# TMCM-1110_V21_eagle.net
KiCad netlist of a schematic drawn in EAGLE
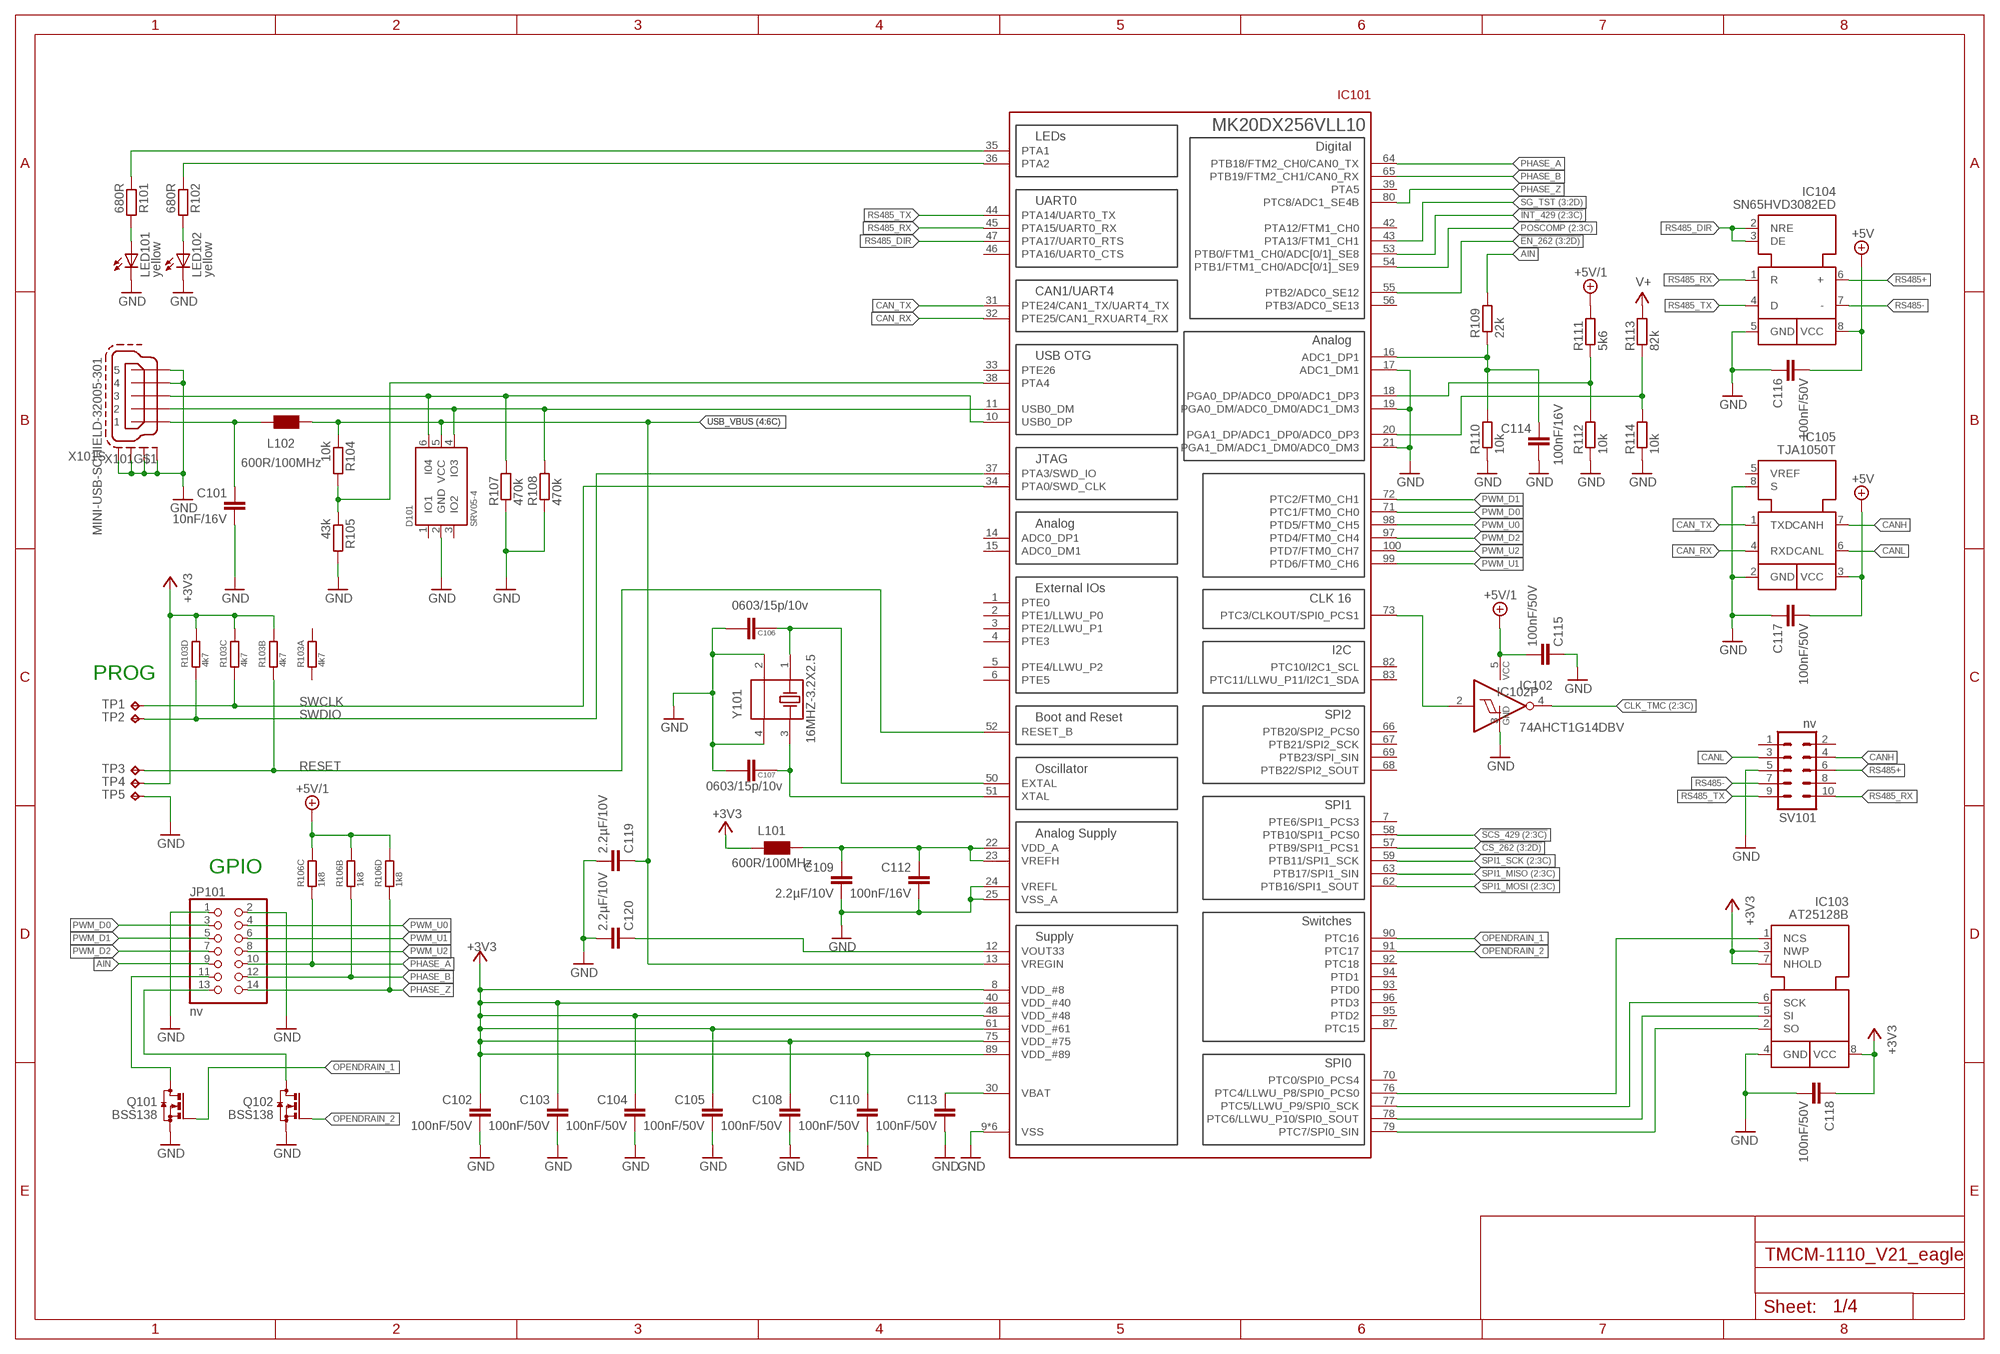
[diagram p0: schematic, sheet 1]
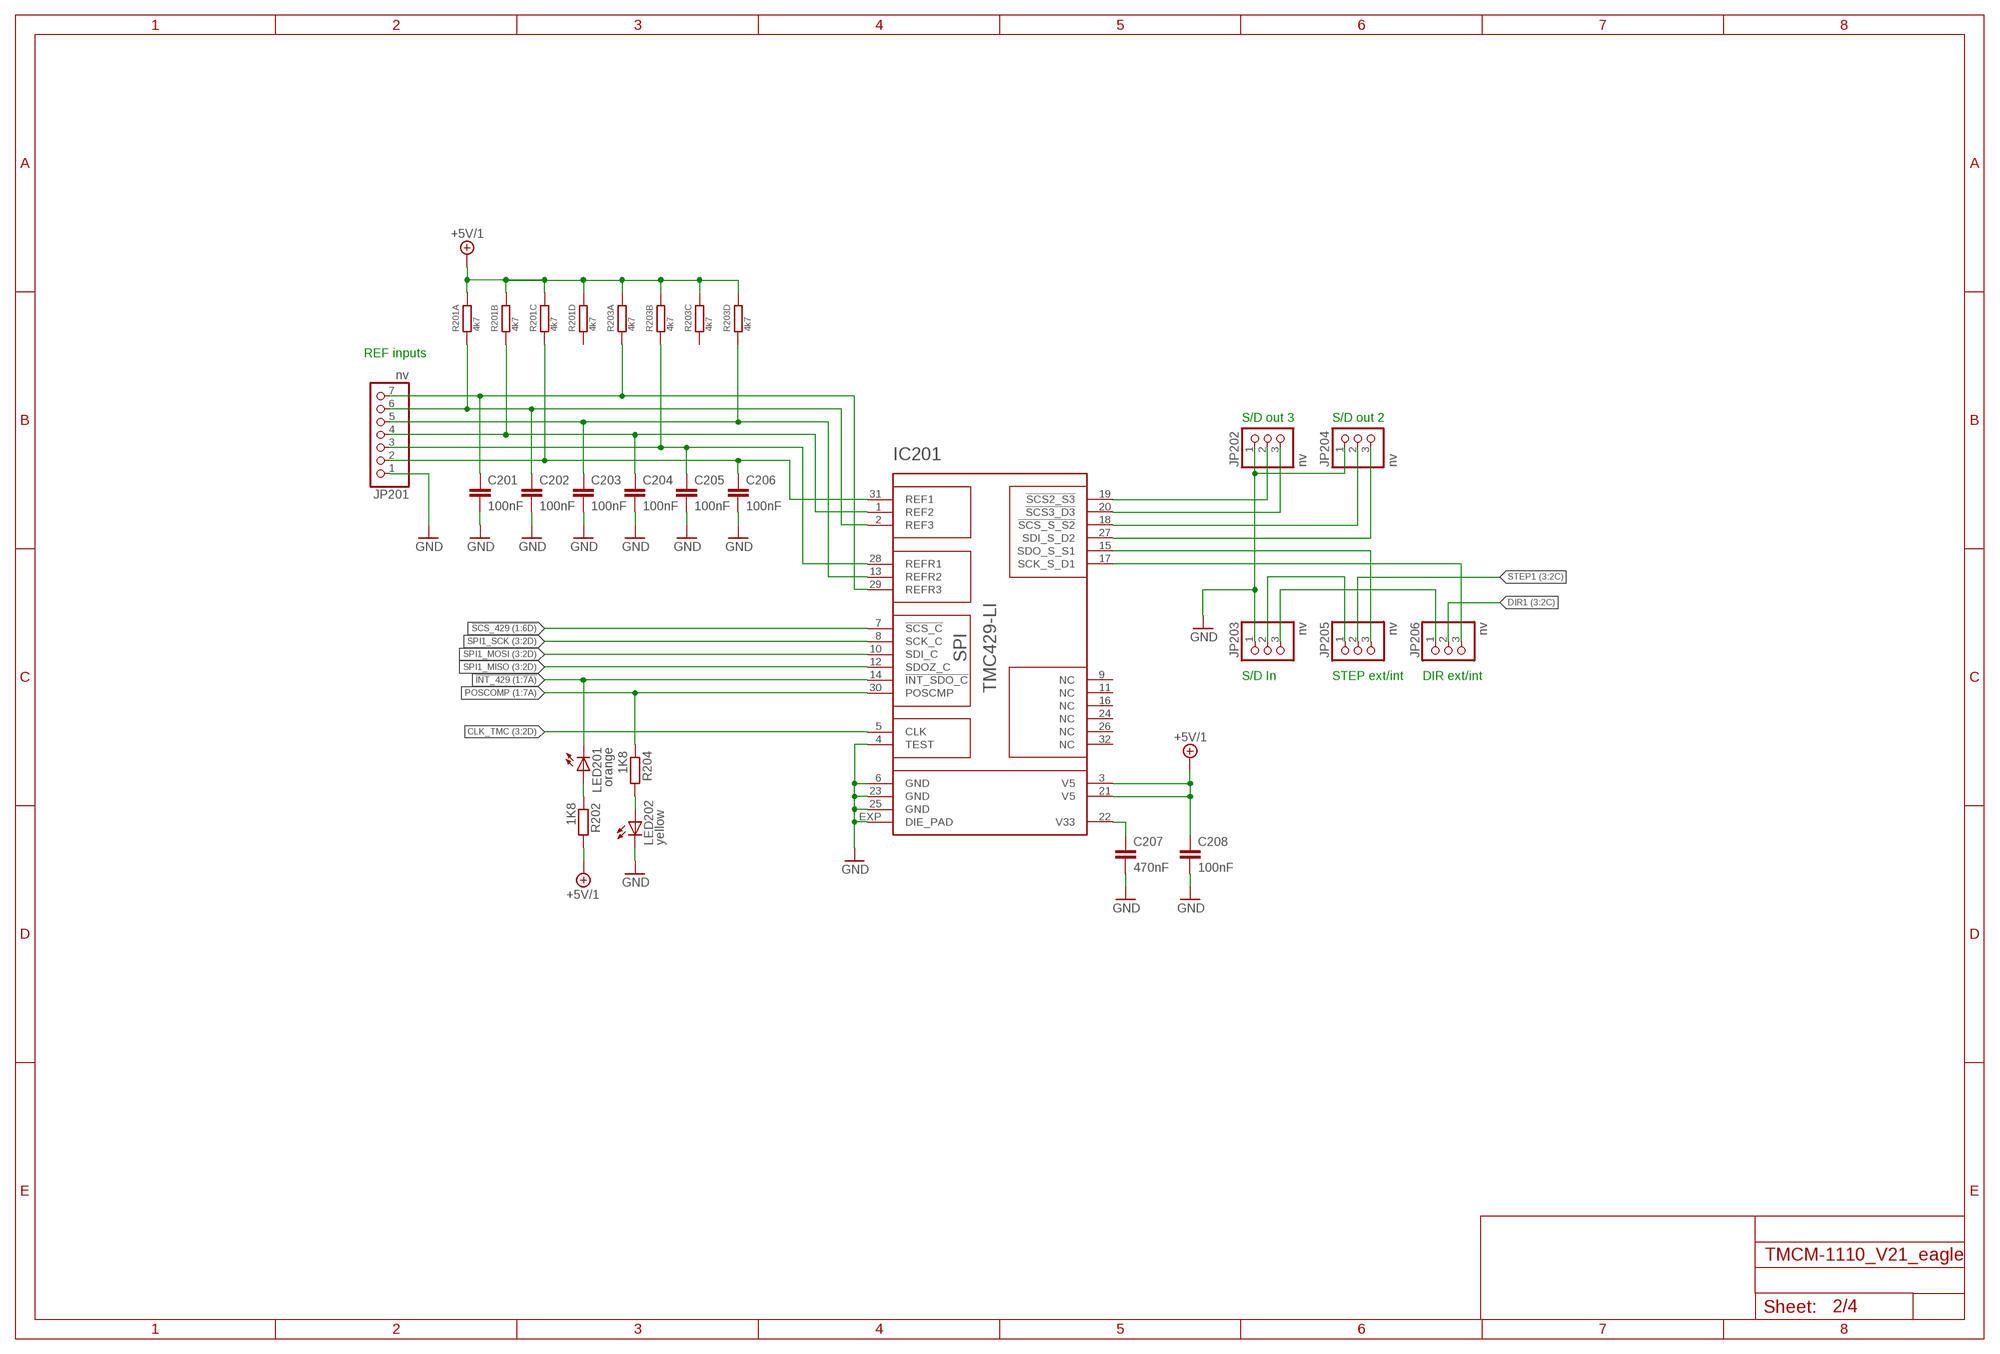
[diagram p1: schematic, sheet 2]
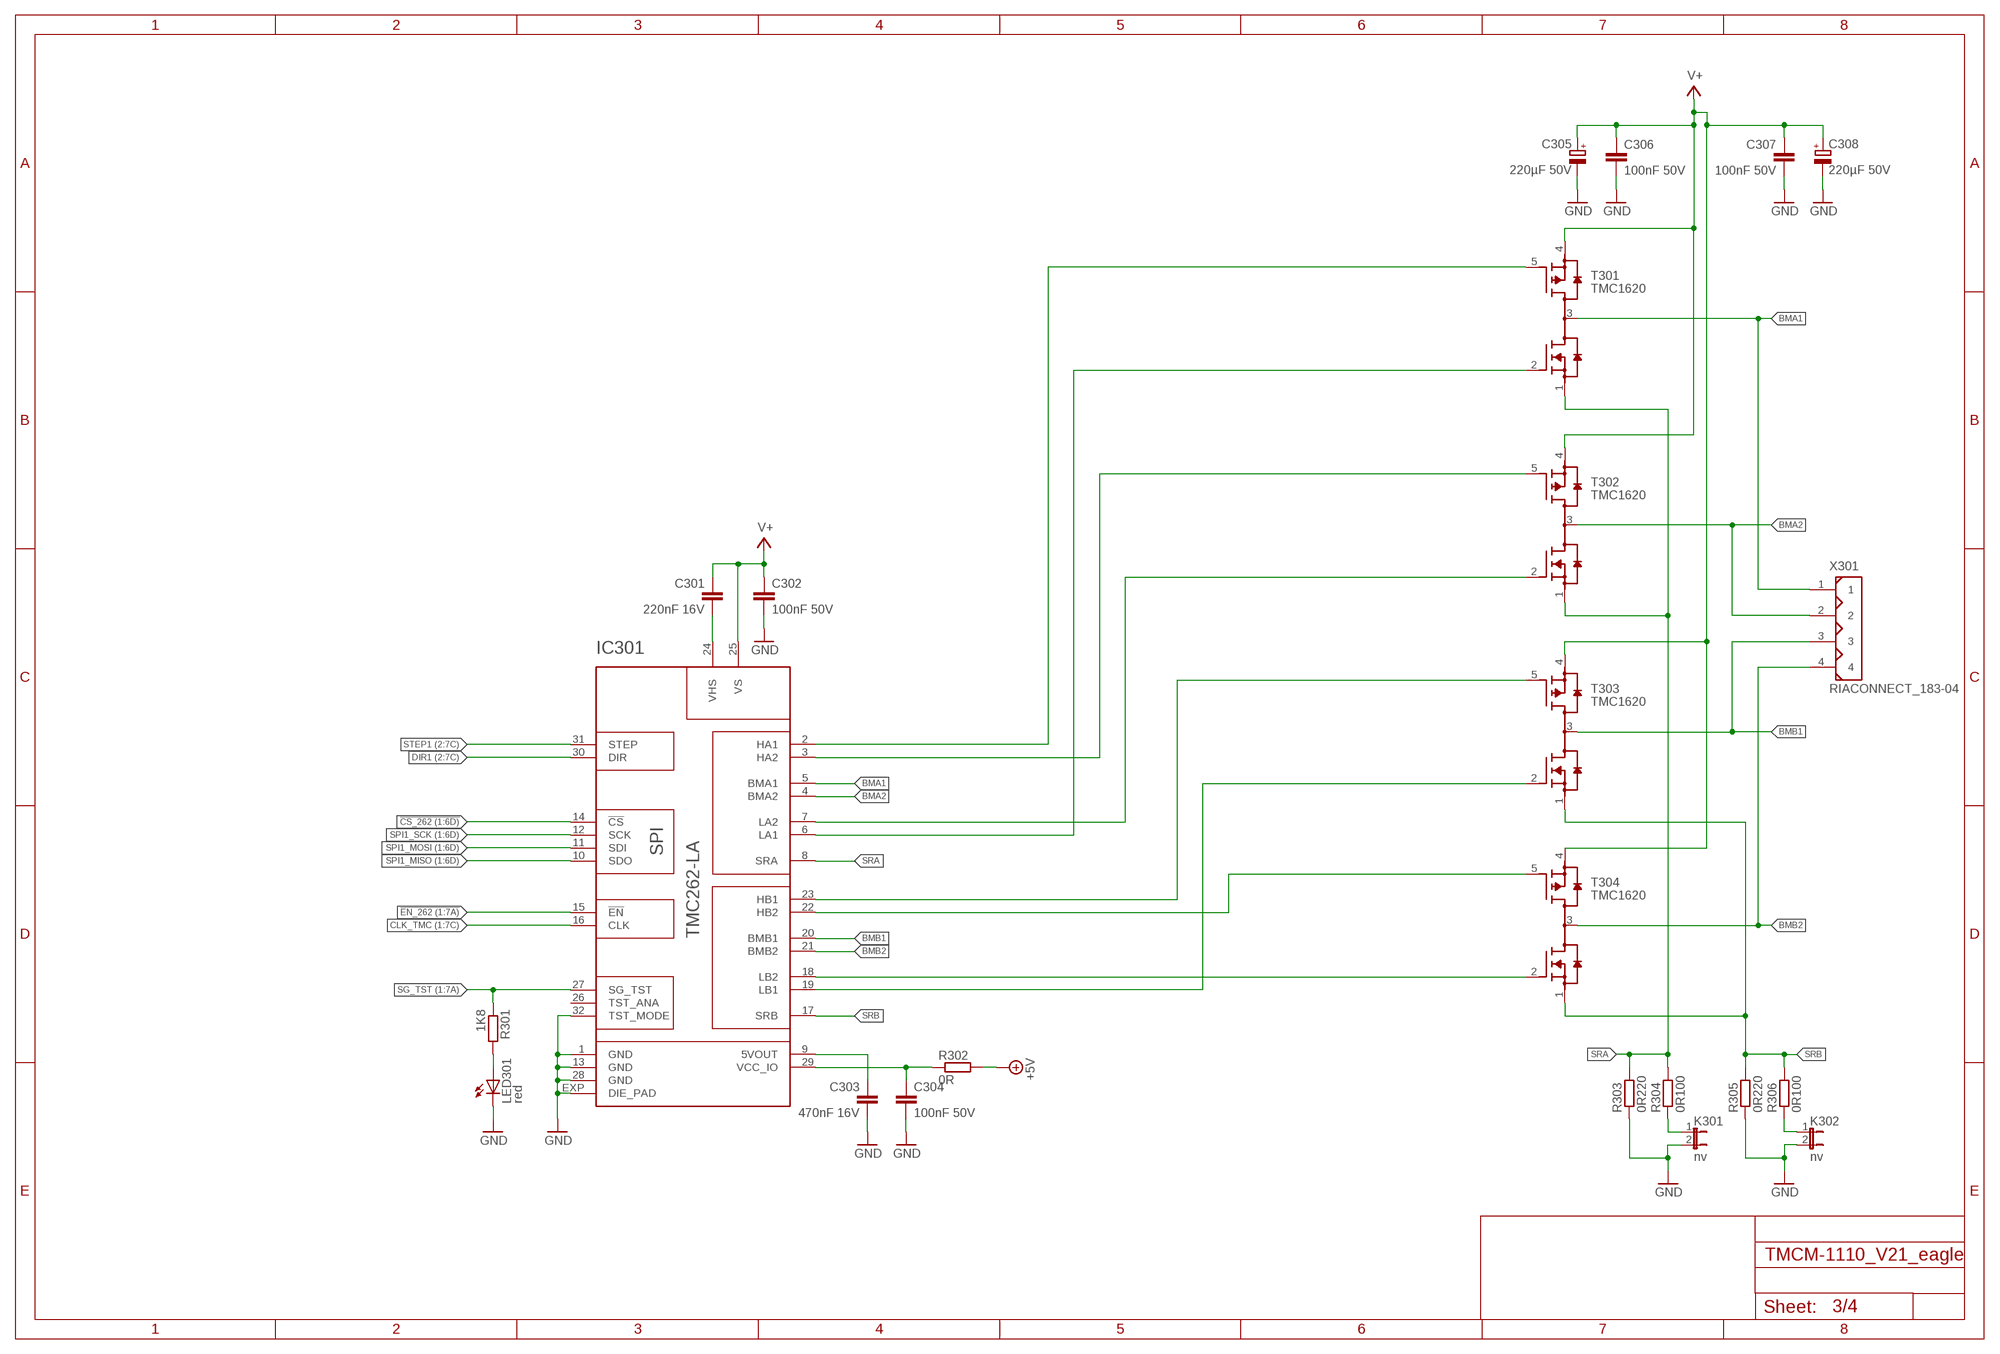
[diagram p2: schematic, sheet 3]
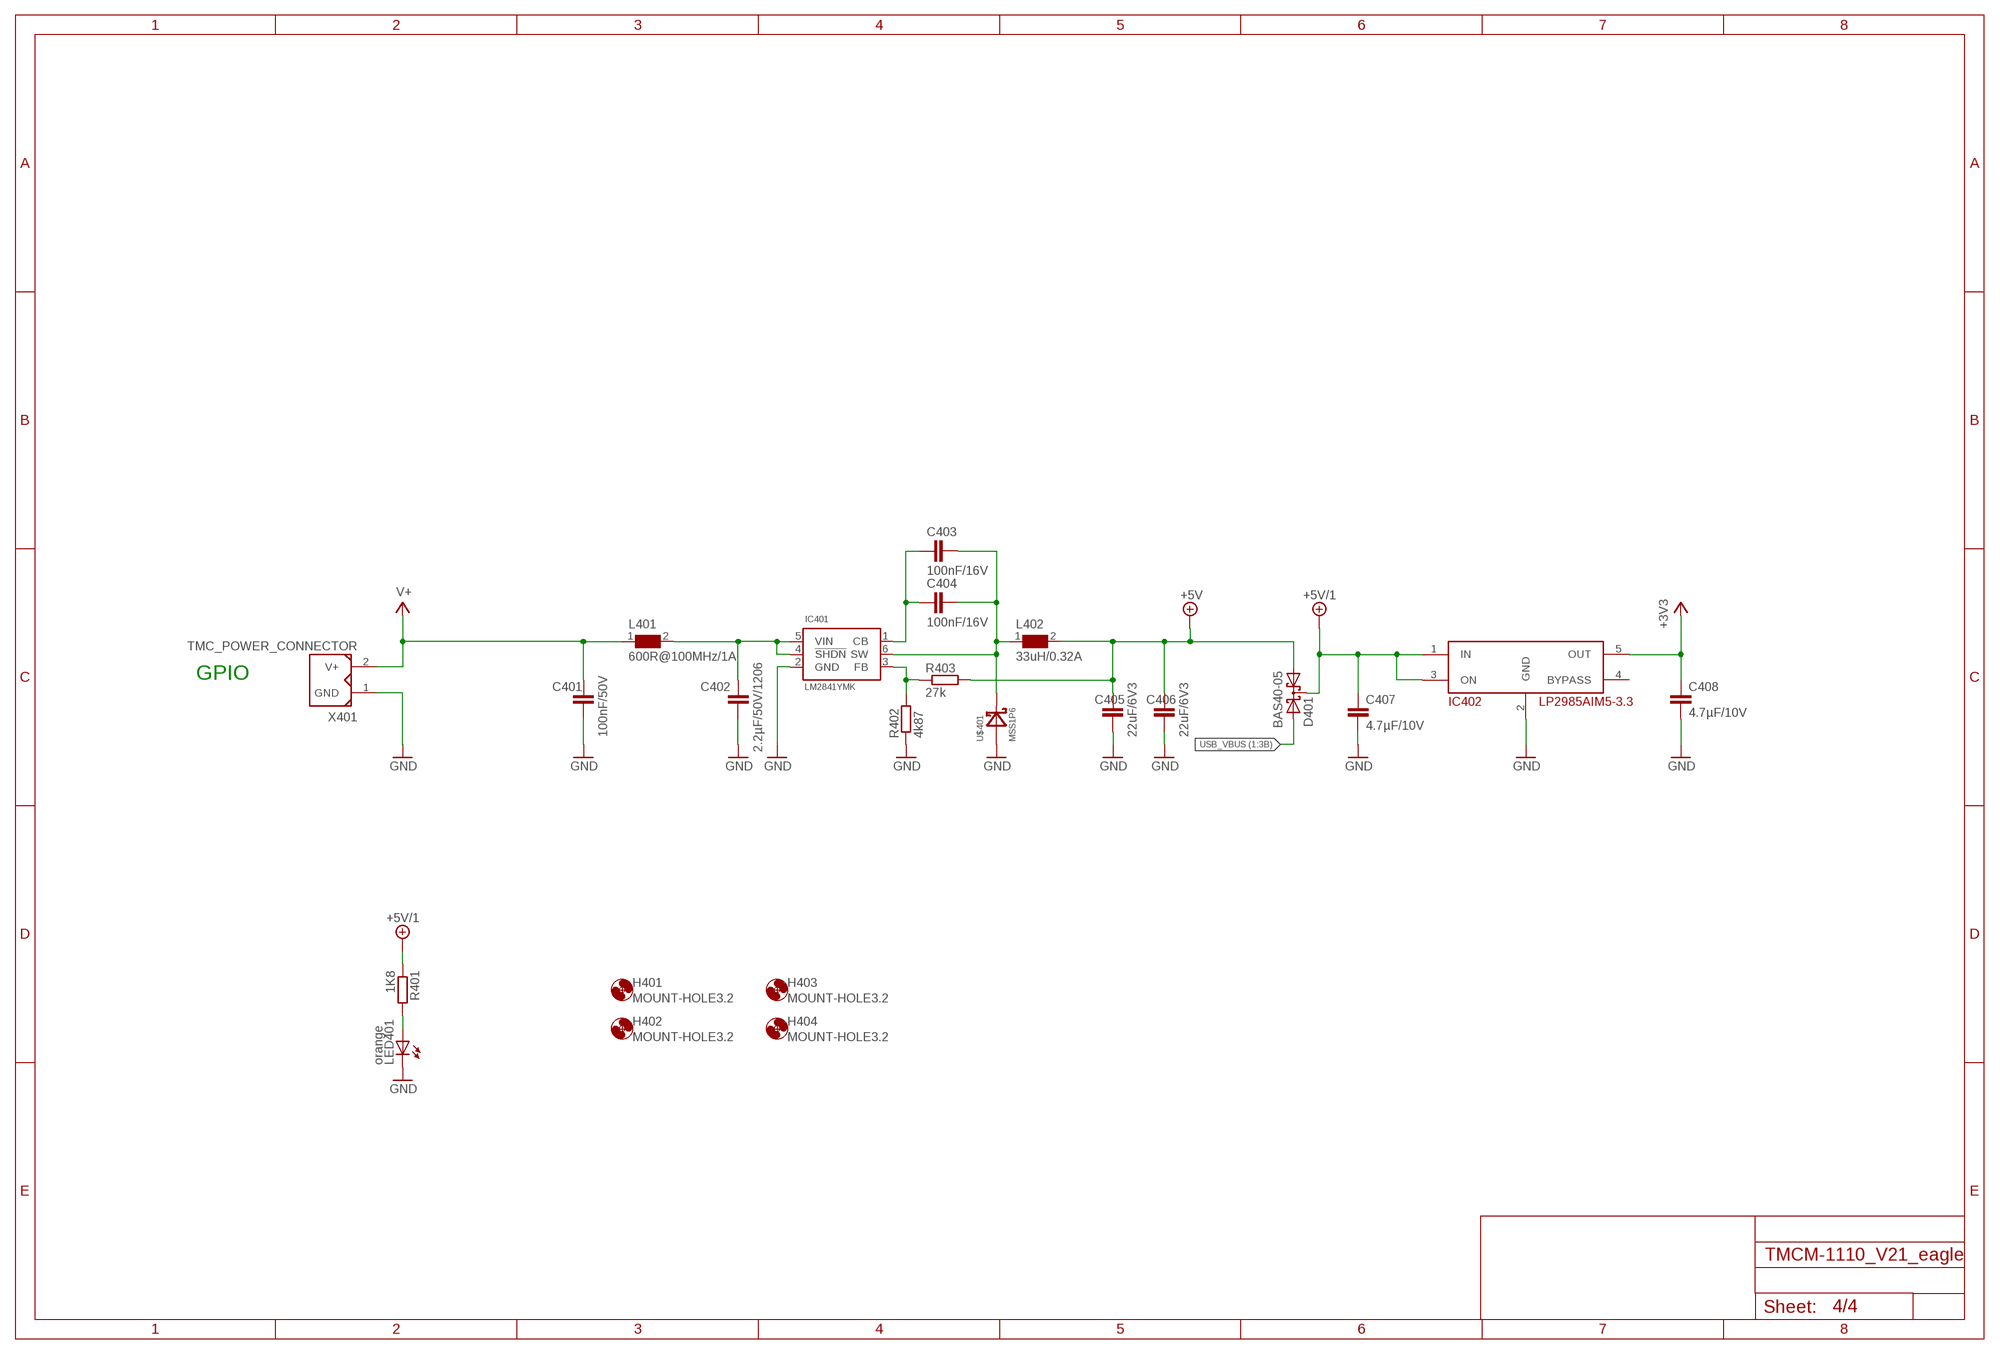
[diagram p3: schematic, sheet 4]

(export (version "E")
  (design (tool "Eeschema 10.0.6"))
  (components
    (comp (ref "C201")
      (value "100nF")
      (footprint "eagle-import:C0603")
      (libsource (lib "eagle-import") (part "C-EUC0603"))
    )
    (comp (ref "C202")
      (value "100nF")
      (footprint "eagle-import:C0603")
      (libsource (lib "eagle-import") (part "C-EUC0603"))
    )
    (comp (ref "C203")
      (value "100nF")
      (footprint "eagle-import:C0603")
      (libsource (lib "eagle-import") (part "C-EUC0603"))
    )
    (comp (ref "C204")
      (value "100nF")
      (footprint "eagle-import:C0603")
      (libsource (lib "eagle-import") (part "C-EUC0603"))
    )
    (comp (ref "C205")
      (value "100nF")
      (footprint "eagle-import:C0603")
      (libsource (lib "eagle-import") (part "C-EUC0603"))
    )
    (comp (ref "C206")
      (value "100nF")
      (footprint "eagle-import:C0603")
      (libsource (lib "eagle-import") (part "C-EUC0603"))
    )
    (comp (ref "C207")
      (value "470nF")
      (footprint "eagle-import:C0603")
      (libsource (lib "eagle-import") (part "C-EUC0603"))
    )
    (comp (ref "C208")
      (value "100nF")
      (footprint "eagle-import:C0603")
      (libsource (lib "eagle-import") (part "C-EUC0603"))
    )
    (comp (ref "IC201")
      (value "TMC429-LI")
      (footprint "eagle-import:QFN32_5X5")
      (libsource (lib "eagle-import") (part "TMC429-LI"))
    )
    (comp (ref "JP201")
      (value "nv")
      (footprint "eagle-import:1X07")
      (libsource (lib "eagle-import") (part "PINHD-1X7"))
    )
    (comp (ref "JP202")
      (value "nv")
      (footprint "eagle-import:1X03")
      (libsource (lib "eagle-import") (part "PINHD-1X3"))
    )
    (comp (ref "JP203")
      (value "nv")
      (footprint "eagle-import:1X03")
      (libsource (lib "eagle-import") (part "PINHD-1X3"))
    )
    (comp (ref "JP204")
      (value "nv")
      (footprint "eagle-import:1X03")
      (libsource (lib "eagle-import") (part "PINHD-1X3"))
    )
    (comp (ref "JP205")
      (value "nv")
      (footprint "eagle-import:1X03")
      (libsource (lib "eagle-import") (part "PINHD-1X3"))
    )
    (comp (ref "JP206")
      (value "nv")
      (footprint "eagle-import:1X03")
      (libsource (lib "eagle-import") (part "PINHD-1X3"))
    )
    (comp (ref "LED201")
      (value "orange")
      (footprint "eagle-import:CHIP-LED0603")
      (libsource (lib "eagle-import") (part "LEDCHIP-LED0603"))
    )
    (comp (ref "LED202")
      (value "yellow")
      (footprint "eagle-import:CHIP-LED0603")
      (libsource (lib "eagle-import") (part "LEDCHIP-LED0603"))
    )
    (comp (ref "R201")
      (value "4k7")
      (footprint "eagle-import:R_4X_1206")
      (libsource (lib "eagle-import") (part "R_NET_4X"))
    )
    (comp (ref "R202")
      (value "1K8")
      (footprint "eagle-import:R0603")
      (libsource (lib "eagle-import") (part "R-EU_R0603"))
    )
    (comp (ref "R203")
      (value "4k7")
      (footprint "eagle-import:R_4X_1206")
      (libsource (lib "eagle-import") (part "R_NET_4X"))
    )
    (comp (ref "R204")
      (value "1K8")
      (footprint "eagle-import:R0603")
      (libsource (lib "eagle-import") (part "R-EU_R0603"))
    )
    (comp (ref "C101")
      (value "10nF/16V")
      (footprint "eagle-import:C0603")
      (libsource (lib "eagle-import") (part "C-EUC0603"))
    )
    (comp (ref "C102")
      (value "100nF/50V")
      (footprint "eagle-import:C0603")
      (libsource (lib "eagle-import") (part "C-EUC0603"))
    )
    (comp (ref "C103")
      (value "100nF/50V")
      (footprint "eagle-import:C0603")
      (libsource (lib "eagle-import") (part "C-EUC0603"))
    )
    (comp (ref "C104")
      (value "100nF/50V")
      (footprint "eagle-import:C0603")
      (libsource (lib "eagle-import") (part "C-EUC0603"))
    )
    (comp (ref "C105")
      (value "100nF/50V")
      (footprint "eagle-import:C0603")
      (libsource (lib "eagle-import") (part "C-EUC0603"))
    )
    (comp (ref "C106")
      (value "0603/15p/10v")
      (footprint "eagle-import:0603")
      (libsource (lib "eagle-import") (part "C/0603"))
    )
    (comp (ref "C107")
      (value "0603/15p/10v")
      (footprint "eagle-import:0603")
      (libsource (lib "eagle-import") (part "C/0603"))
    )
    (comp (ref "C108")
      (value "100nF/50V")
      (footprint "eagle-import:C0603")
      (libsource (lib "eagle-import") (part "C-EUC0603"))
    )
    (comp (ref "C109")
      (value "2.2µF/10V")
      (footprint "eagle-import:C0603")
      (libsource (lib "eagle-import") (part "C-EUC0603"))
    )
    (comp (ref "C110")
      (value "100nF/50V")
      (footprint "eagle-import:C0603")
      (libsource (lib "eagle-import") (part "C-EUC0603"))
    )
    (comp (ref "C112")
      (value "100nF/16V")
      (footprint "eagle-import:C0603")
      (libsource (lib "eagle-import") (part "C-EUC0603"))
    )
    (comp (ref "C113")
      (value "100nF/50V")
      (footprint "eagle-import:C0603")
      (libsource (lib "eagle-import") (part "C-EUC0603"))
    )
    (comp (ref "C114")
      (value "100nF/16V")
      (footprint "eagle-import:C0603")
      (libsource (lib "eagle-import") (part "C-EUC0603"))
    )
    (comp (ref "C115")
      (value "100nF/50V")
      (footprint "eagle-import:C0603")
      (libsource (lib "eagle-import") (part "C-EUC0603"))
    )
    (comp (ref "C116")
      (value "100nF/50V")
      (footprint "eagle-import:C0603")
      (libsource (lib "eagle-import") (part "C-EUC0603"))
    )
    (comp (ref "C117")
      (value "100nF/50V")
      (footprint "eagle-import:C0603")
      (libsource (lib "eagle-import") (part "C-EUC0603"))
    )
    (comp (ref "C118")
      (value "100nF/50V")
      (footprint "eagle-import:C0603")
      (libsource (lib "eagle-import") (part "C-EUC0603"))
    )
    (comp (ref "C119")
      (value "2.2µF/10V")
      (footprint "eagle-import:C0603")
      (libsource (lib "eagle-import") (part "C-EUC0603"))
    )
    (comp (ref "C120")
      (value "2.2µF/10V")
      (footprint "eagle-import:C0603")
      (libsource (lib "eagle-import") (part "C-EUC0603"))
    )
    (comp (ref "D101")
      (value "SRV05-4")
      (footprint "eagle-import:TMC_SOT23-6")
      (libsource (lib "eagle-import") (part "SRV05-4"))
    )
    (comp (ref "IC101")
      (value "MK20DX256VLL10")
      (footprint "eagle-import:TMC_LQFP100")
      (libsource (lib "eagle-import") (part "MK20DX256VLL10"))
    )
    (comp (ref "IC102")
      (value "74AHCT1G14DBV")
      (footprint "eagle-import:SOT23-5")
      (libsource (lib "eagle-import") (part "741G14DBVAHCT"))
    )
    (comp (ref "IC103")
      (value "AT25128B")
      (footprint "eagle-import:SO8")
      (libsource (lib "eagle-import") (part "AT25128B"))
    )
    (comp (ref "IC104")
      (value "SN65HVD3082ED")
      (footprint "eagle-import:SO8")
      (libsource (lib "eagle-import") (part "SN65HVD3082ED"))
    )
    (comp (ref "IC105")
      (value "TJA1050T")
      (footprint "eagle-import:SO8")
      (libsource (lib "eagle-import") (part "TJA1050T"))
    )
    (comp (ref "JP101")
      (value "nv")
      (footprint "eagle-import:2X07")
      (libsource (lib "eagle-import") (part "PINHD-2X7"))
    )
    (comp (ref "L101")
      (value "600R/100MHz")
      (footprint "eagle-import:0603")
      (libsource (lib "eagle-import") (part "wuerth-elektronik_WE-CBF_0603"))
    )
    (comp (ref "L102")
      (value "600R/100MHz")
      (footprint "eagle-import:0603")
      (libsource (lib "eagle-import") (part "wuerth-elektronik_WE-CBF_0603"))
    )
    (comp (ref "LED101")
      (value "yellow")
      (footprint "eagle-import:CHIP-LED0603")
      (libsource (lib "eagle-import") (part "LEDCHIP-LED0603"))
    )
    (comp (ref "LED102")
      (value "yellow")
      (footprint "eagle-import:CHIP-LED0603")
      (libsource (lib "eagle-import") (part "LEDCHIP-LED0603"))
    )
    (comp (ref "Q101")
      (value "BSS138")
      (footprint "eagle-import:SOT23")
      (libsource (lib "eagle-import") (part "BSS138"))
    )
    (comp (ref "Q102")
      (value "BSS138")
      (footprint "eagle-import:SOT23")
      (libsource (lib "eagle-import") (part "BSS138"))
    )
    (comp (ref "R101")
      (value "680R")
      (footprint "eagle-import:R0603")
      (libsource (lib "eagle-import") (part "R-EU_R0603"))
    )
    (comp (ref "R102")
      (value "680R")
      (footprint "eagle-import:R0603")
      (libsource (lib "eagle-import") (part "R-EU_R0603"))
    )
    (comp (ref "R103")
      (value "4k7")
      (footprint "eagle-import:R_4X_1206")
      (libsource (lib "eagle-import") (part "R_NET_4X"))
    )
    (comp (ref "R104")
      (value "10k")
      (footprint "eagle-import:R0603")
      (libsource (lib "eagle-import") (part "R-EU_R0603"))
    )
    (comp (ref "R105")
      (value "43k")
      (footprint "eagle-import:R0603")
      (libsource (lib "eagle-import") (part "R-EU_R0603"))
    )
    (comp (ref "R106")
      (value "1k8")
      (footprint "eagle-import:R_4X_1206")
      (libsource (lib "eagle-import") (part "R_NET_4X"))
    )
    (comp (ref "R107")
      (value "470k")
      (footprint "eagle-import:R0603")
      (libsource (lib "eagle-import") (part "R-EU_R0603"))
    )
    (comp (ref "R108")
      (value "470k")
      (footprint "eagle-import:R0603")
      (libsource (lib "eagle-import") (part "R-EU_R0603"))
    )
    (comp (ref "R109")
      (value "22k")
      (footprint "eagle-import:R0603")
      (libsource (lib "eagle-import") (part "R-EU_R0603"))
    )
    (comp (ref "R110")
      (value "10k")
      (footprint "eagle-import:R0603")
      (libsource (lib "eagle-import") (part "R-EU_R0603"))
    )
    (comp (ref "R111")
      (value "5k6")
      (footprint "eagle-import:R0603")
      (libsource (lib "eagle-import") (part "R-EU_R0603"))
    )
    (comp (ref "R112")
      (value "10k")
      (footprint "eagle-import:R0603")
      (libsource (lib "eagle-import") (part "R-EU_R0603"))
    )
    (comp (ref "R113")
      (value "82k")
      (footprint "eagle-import:R0603")
      (libsource (lib "eagle-import") (part "R-EU_R0603"))
    )
    (comp (ref "R114")
      (value "10k")
      (footprint "eagle-import:R0603")
      (libsource (lib "eagle-import") (part "R-EU_R0603"))
    )
    (comp (ref "SV101")
      (value "nv")
      (footprint "eagle-import:ML10")
      (libsource (lib "eagle-import") (part "ML10"))
    )
    (comp (ref "TP1")
      (value "TPTP15SQ")
      (footprint "eagle-import:TP15SQ")
      (libsource (lib "eagle-import") (part "TPTP15SQ"))
    )
    (comp (ref "TP2")
      (value "TPTP15SQ")
      (footprint "eagle-import:TP15SQ")
      (libsource (lib "eagle-import") (part "TPTP15SQ"))
    )
    (comp (ref "TP3")
      (value "TPTP15SQ")
      (footprint "eagle-import:TP15SQ")
      (libsource (lib "eagle-import") (part "TPTP15SQ"))
    )
    (comp (ref "TP4")
      (value "TPTP15SQ")
      (footprint "eagle-import:TP15SQ")
      (libsource (lib "eagle-import") (part "TPTP15SQ"))
    )
    (comp (ref "TP5")
      (value "TPTP15SQ")
      (footprint "eagle-import:TP15SQ")
      (libsource (lib "eagle-import") (part "TPTP15SQ"))
    )
    (comp (ref "X101")
      (value "MINI-USB-SCHIELD-32005-301")
      (footprint "eagle-import:32005-301")
      (libsource (lib "eagle-import") (part "MINI-USB-SCHIELD-32005-301"))
    )
    (comp (ref "Y101")
      (value "16MHZ-3.2X2.5")
      (footprint "eagle-import:MYLIB_FA-238")
      (libsource (lib "eagle-import") (part "MYLIB_CRYSTAL-16MHZ-3.2X2.5"))
    )
    (comp (ref "C301")
      (value "220nF 16V")
      (footprint "eagle-import:C0603")
      (libsource (lib "eagle-import") (part "C-EUC0603"))
    )
    (comp (ref "C302")
      (value "100nF 50V")
      (footprint "eagle-import:C0603")
      (libsource (lib "eagle-import") (part "C-EUC0603"))
    )
    (comp (ref "C303")
      (value "470nF 16V")
      (footprint "eagle-import:C0603")
      (libsource (lib "eagle-import") (part "C-EUC0603"))
    )
    (comp (ref "C304")
      (value "100nF 50V")
      (footprint "eagle-import:C0603")
      (libsource (lib "eagle-import") (part "C-EUC0603"))
    )
    (comp (ref "C305")
      (value "220µF 50V")
      (footprint "eagle-import:E5-10,5")
      (libsource (lib "eagle-import") (part "CPOL-EUE5-10.5"))
    )
    (comp (ref "C306")
      (value "100nF 50V")
      (footprint "eagle-import:C0603")
      (libsource (lib "eagle-import") (part "C-EUC0603"))
    )
    (comp (ref "C307")
      (value "100nF 50V")
      (footprint "eagle-import:C0603")
      (libsource (lib "eagle-import") (part "C-EUC0603"))
    )
    (comp (ref "C308")
      (value "220µF 50V")
      (footprint "eagle-import:E5-10,5")
      (libsource (lib "eagle-import") (part "CPOL-EUE5-10.5"))
    )
    (comp (ref "IC301")
      (value "TMC262-LA")
      (footprint "eagle-import:QFN32_5X5")
      (libsource (lib "eagle-import") (part "TMC262-LA"))
    )
    (comp (ref "K301")
      (value "nv")
      (footprint "eagle-import:JP1")
      (libsource (lib "eagle-import") (part "JP1E"))
    )
    (comp (ref "K302")
      (value "nv")
      (footprint "eagle-import:JP1")
      (libsource (lib "eagle-import") (part "JP1E"))
    )
    (comp (ref "LED301")
      (value "red")
      (footprint "eagle-import:CHIP-LED0603")
      (libsource (lib "eagle-import") (part "LEDCHIP-LED0603"))
    )
    (comp (ref "R301")
      (value "1K8")
      (footprint "eagle-import:R0603")
      (libsource (lib "eagle-import") (part "R-EU_R0603"))
    )
    (comp (ref "R302")
      (value "0R")
      (footprint "eagle-import:R0603")
      (libsource (lib "eagle-import") (part "R-EU_R0603"))
    )
    (comp (ref "R303")
      (value "0R220")
      (footprint "eagle-import:R1206")
      (libsource (lib "eagle-import") (part "R-EU_R1206"))
    )
    (comp (ref "R304")
      (value "0R100")
      (footprint "eagle-import:R1206")
      (libsource (lib "eagle-import") (part "R-EU_R1206"))
    )
    (comp (ref "R305")
      (value "0R220")
      (footprint "eagle-import:R1206")
      (libsource (lib "eagle-import") (part "R-EU_R1206"))
    )
    (comp (ref "R306")
      (value "0R100")
      (footprint "eagle-import:R1206")
      (libsource (lib "eagle-import") (part "R-EU_R1206"))
    )
    (comp (ref "T301")
      (value "TMC1620")
      (footprint "eagle-import:DUAL_DPAK_4L")
      (libsource (lib "eagle-import") (part "TMC1620"))
    )
    (comp (ref "T302")
      (value "TMC1620")
      (footprint "eagle-import:DUAL_DPAK_4L")
      (libsource (lib "eagle-import") (part "TMC1620"))
    )
    (comp (ref "T303")
      (value "TMC1620")
      (footprint "eagle-import:DUAL_DPAK_4L")
      (libsource (lib "eagle-import") (part "TMC1620"))
    )
    (comp (ref "T304")
      (value "TMC1620")
      (footprint "eagle-import:DUAL_DPAK_4L")
      (libsource (lib "eagle-import") (part "TMC1620"))
    )
    (comp (ref "X301")
      (value "RIACONNECT_183-04")
      (footprint "eagle-import:RIACONNECT_183-04")
      (libsource (lib "eagle-import") (part "RIACONNECT_183-04"))
    )
    (comp (ref "C401")
      (value "100nF/50V")
      (footprint "eagle-import:C0603")
      (libsource (lib "eagle-import") (part "C-EUC0603"))
    )
    (comp (ref "C402")
      (value "2.2µF/50V/1206")
      (footprint "eagle-import:C1206")
      (libsource (lib "eagle-import") (part "C-EUC1206"))
    )
    (comp (ref "C403")
      (value "100nF/16V")
      (footprint "eagle-import:C0603")
      (libsource (lib "eagle-import") (part "C-EUC0603"))
    )
    (comp (ref "C404")
      (value "100nF/16V")
      (footprint "eagle-import:C0603")
      (libsource (lib "eagle-import") (part "C-EUC0603"))
    )
    (comp (ref "C405")
      (value "22uF/6V3")
      (footprint "eagle-import:C0805")
      (libsource (lib "eagle-import") (part "C-EUC0805"))
    )
    (comp (ref "C406")
      (value "22uF/6V3")
      (footprint "eagle-import:C0805")
      (libsource (lib "eagle-import") (part "C-EUC0805"))
    )
    (comp (ref "C407")
      (value "4.7µF/10V")
      (footprint "eagle-import:C0603")
      (libsource (lib "eagle-import") (part "C-EUC0603"))
    )
    (comp (ref "C408")
      (value "4.7µF/10V")
      (footprint "eagle-import:C0603")
      (libsource (lib "eagle-import") (part "C-EUC0603"))
    )
    (comp (ref "D401")
      (value "BAS40-05")
      (footprint "eagle-import:SOT23")
      (libsource (lib "eagle-import") (part "BAS40-05"))
    )
    (comp (ref "H401")
      (value "MOUNT-HOLE3.2")
      (footprint "eagle-import:3,2")
      (libsource (lib "eagle-import") (part "MOUNT-HOLE3.2"))
    )
    (comp (ref "H402")
      (value "MOUNT-HOLE3.2")
      (footprint "eagle-import:3,2")
      (libsource (lib "eagle-import") (part "MOUNT-HOLE3.2"))
    )
    (comp (ref "H403")
      (value "MOUNT-HOLE3.2")
      (footprint "eagle-import:3,2")
      (libsource (lib "eagle-import") (part "MOUNT-HOLE3.2"))
    )
    (comp (ref "H404")
      (value "MOUNT-HOLE3.2")
      (footprint "eagle-import:3,2")
      (libsource (lib "eagle-import") (part "MOUNT-HOLE3.2"))
    )
    (comp (ref "IC401")
      (value "LM2841YMK")
      (footprint "eagle-import:TMC_SOT23-6")
      (libsource (lib "eagle-import") (part "LM2841YMK"))
    )
    (comp (ref "IC402")
      (value "LP2985AIM5-3.3")
      (footprint "eagle-import:SOT23-5")
      (libsource (lib "eagle-import") (part "LP2985AIM5-3.3"))
    )
    (comp (ref "L401")
      (value "600R@100MHz/1A")
      (footprint "eagle-import:0603")
      (libsource (lib "eagle-import") (part "WE-CBF_0603"))
    )
    (comp (ref "L402")
      (value "33uH/0.32A")
      (footprint "eagle-import:WE-TPC_3816")
      (libsource (lib "eagle-import") (part "WE-TPC_3816"))
    )
    (comp (ref "LED401")
      (value "orange")
      (footprint "eagle-import:CHIP-LED0603")
      (libsource (lib "eagle-import") (part "LEDCHIP-LED0603"))
    )
    (comp (ref "R401")
      (value "1K8")
      (footprint "eagle-import:R0603")
      (libsource (lib "eagle-import") (part "R-EU_R0603"))
    )
    (comp (ref "R402")
      (value "4k87")
      (footprint "eagle-import:R0603")
      (libsource (lib "eagle-import") (part "R-EU_R0603"))
    )
    (comp (ref "R403")
      (value "27k")
      (footprint "eagle-import:R0603")
      (libsource (lib "eagle-import") (part "R-EU_R0603"))
    )
    (comp (ref "U$401")
      (value "MSS1P6")
      (footprint "eagle-import:MICRO_SMP")
      (libsource (lib "eagle-import") (part "MSS1P6"))
    )
    (comp (ref "X401")
      (value "TMC_POWER_CONNECTOR")
      (footprint "eagle-import:RIACONNECT_320-02")
      (libsource (lib "eagle-import") (part "TMC_POWER_CONNECTOR"))
    )
  )
  (nets
    (net (code "1") (name "+3V3") (class "Default")
      (node (ref "C102") (pin "1") (pinfunction "1_1") (pintype "passive"))
      (node (ref "C103") (pin "1") (pinfunction "1_1") (pintype "passive"))
      (node (ref "C104") (pin "1") (pinfunction "1_1") (pintype "passive"))
      (node (ref "C105") (pin "1") (pinfunction "1_1") (pintype "passive"))
      (node (ref "C108") (pin "1") (pinfunction "1_1") (pintype "passive"))
      (node (ref "C110") (pin "1") (pinfunction "1_1") (pintype "passive"))
      (node (ref "C118") (pin "1") (pinfunction "1_1") (pintype "passive"))
      (node (ref "C408") (pin "1") (pinfunction "1_1") (pintype "passive"))
      (node (ref "IC101") (pin "40") (pinfunction "VDD_#40_40") (pintype "bidirectional"))
      (node (ref "IC101") (pin "48") (pinfunction "VDD_#48_48") (pintype "bidirectional"))
      (node (ref "IC101") (pin "61") (pinfunction "VDD_#61_61") (pintype "bidirectional"))
      (node (ref "IC101") (pin "75") (pinfunction "VDD_#75_75") (pintype "bidirectional"))
      (node (ref "IC101") (pin "8") (pinfunction "VDD_#8_8") (pintype "bidirectional"))
      (node (ref "IC101") (pin "89") (pinfunction "VDD_#89_89") (pintype "bidirectional"))
      (node (ref "IC103") (pin "3") (pinfunction "NWP_3") (pintype "bidirectional"))
      (node (ref "IC103") (pin "7") (pinfunction "NHOLD_7") (pintype "bidirectional"))
      (node (ref "IC103") (pin "8") (pinfunction "VCC_8") (pintype "bidirectional"))
      (node (ref "IC402") (pin "5") (pinfunction "OUT_5") (pintype "bidirectional"))
      (node (ref "L101") (pin "1") (pinfunction "1_1") (pintype "passive"))
      (node (ref "R103") (pin "P$5") (pinfunction "2_P$5") (pintype "bidirectional"))
      (node (ref "R103") (pin "P$6") (pinfunction "2_P$6") (pintype "bidirectional"))
      (node (ref "R103") (pin "P$7") (pinfunction "2_P$7") (pintype "bidirectional"))
      (node (ref "TP4") (pin "TP") (pinfunction "TP_TP") (pintype "input"))
    )
    (net (code "2") (name "+5V") (class "Default")
      (node (ref "C116") (pin "2") (pinfunction "2_2") (pintype "passive"))
      (node (ref "C117") (pin "2") (pinfunction "2_2") (pintype "passive"))
      (node (ref "C405") (pin "1") (pinfunction "1_1") (pintype "passive"))
      (node (ref "C406") (pin "1") (pinfunction "1_1") (pintype "passive"))
      (node (ref "D401") (pin "1") (pinfunction "A1_1") (pintype "passive"))
      (node (ref "IC104") (pin "8") (pinfunction "VCC_8") (pintype "bidirectional"))
      (node (ref "IC105") (pin "3") (pinfunction "VCC_3") (pintype "bidirectional"))
      (node (ref "L402") (pin "2") (pinfunction "2_2") (pintype "passive"))
      (node (ref "R302") (pin "2") (pinfunction "2_2") (pintype "passive"))
      (node (ref "R403") (pin "2") (pinfunction "2_2") (pintype "passive"))
    )
    (net (code "3") (name "+5V{slash}1") (class "Default")
      (node (ref "C115") (pin "2") (pinfunction "2_2") (pintype "passive"))
      (node (ref "C208") (pin "1") (pinfunction "1_1") (pintype "passive"))
      (node (ref "C407") (pin "1") (pinfunction "1_1") (pintype "passive"))
      (node (ref "D401") (pin "3") (pinfunction "C_3") (pintype "passive"))
      (node (ref "IC102") (pin "5") (pinfunction "VCC_5") (pintype "power_in"))
      (node (ref "IC201") (pin "21") (pinfunction "V5_21") (pintype "input"))
      (node (ref "IC201") (pin "3") (pinfunction "V5_3") (pintype "input"))
      (node (ref "IC402") (pin "1") (pinfunction "IN_1") (pintype "bidirectional"))
      (node (ref "IC402") (pin "3") (pinfunction "ON_3") (pintype "bidirectional"))
      (node (ref "R106") (pin "P$5") (pinfunction "2_P$5") (pintype "bidirectional"))
      (node (ref "R106") (pin "P$6") (pinfunction "2_P$6") (pintype "bidirectional"))
      (node (ref "R106") (pin "P$7") (pinfunction "2_P$7") (pintype "bidirectional"))
      (node (ref "R111") (pin "2") (pinfunction "2_2") (pintype "passive"))
      (node (ref "R201") (pin "P$5") (pinfunction "2_P$5") (pintype "bidirectional"))
      (node (ref "R201") (pin "P$6") (pinfunction "2_P$6") (pintype "bidirectional"))
      (node (ref "R201") (pin "P$7") (pinfunction "2_P$7") (pintype "bidirectional"))
      (node (ref "R201") (pin "P$8") (pinfunction "2_P$8") (pintype "bidirectional"))
      (node (ref "R202") (pin "2") (pinfunction "2_2") (pintype "passive"))
      (node (ref "R203") (pin "P$5") (pinfunction "2_P$5") (pintype "bidirectional"))
      (node (ref "R203") (pin "P$6") (pinfunction "2_P$6") (pintype "bidirectional"))
      (node (ref "R203") (pin "P$7") (pinfunction "2_P$7") (pintype "bidirectional"))
      (node (ref "R203") (pin "P$8") (pinfunction "2_P$8") (pintype "bidirectional"))
      (node (ref "R401") (pin "1") (pinfunction "1_1") (pintype "passive"))
    )
    (net (code "4") (name "AIN") (class "Default")
      (node (ref "JP101") (pin "9") (pinfunction "9_9") (pintype "passive"))
      (node (ref "R109") (pin "2") (pinfunction "2_2") (pintype "passive"))
    )
    (net (code "5") (name "BMA1") (class "Default")
      (node (ref "IC301") (pin "5") (pinfunction "BMA1_5") (pintype "input"))
      (node (ref "T301") (pin "3") (pinfunction "D_NP_3") (pintype "bidirectional"))
      (node (ref "X301") (pin "1") (pinfunction "1_1") (pintype "bidirectional"))
    )
    (net (code "6") (name "BMA2") (class "Default")
      (node (ref "IC301") (pin "4") (pinfunction "BMA2_4") (pintype "input"))
      (node (ref "T302") (pin "3") (pinfunction "D_NP_3") (pintype "bidirectional"))
      (node (ref "X301") (pin "2") (pinfunction "2_2") (pintype "bidirectional"))
    )
    (net (code "7") (name "BMB1") (class "Default")
      (node (ref "IC301") (pin "20") (pinfunction "BMB1_20") (pintype "input"))
      (node (ref "T303") (pin "3") (pinfunction "D_NP_3") (pintype "bidirectional"))
      (node (ref "X301") (pin "3") (pinfunction "3_3") (pintype "bidirectional"))
    )
    (net (code "8") (name "BMB2") (class "Default")
      (node (ref "IC301") (pin "21") (pinfunction "BMB2_21") (pintype "input"))
      (node (ref "T304") (pin "3") (pinfunction "D_NP_3") (pintype "bidirectional"))
      (node (ref "X301") (pin "4") (pinfunction "4_4") (pintype "bidirectional"))
    )
    (net (code "9") (name "CANH") (class "Default")
      (node (ref "IC105") (pin "7") (pinfunction "CANH_7") (pintype "bidirectional"))
      (node (ref "SV101") (pin "4") (pinfunction "4_4") (pintype "passive"))
    )
    (net (code "10") (name "CANL") (class "Default")
      (node (ref "IC105") (pin "6") (pinfunction "CANL_6") (pintype "bidirectional"))
      (node (ref "SV101") (pin "3") (pinfunction "3_3") (pintype "passive"))
    )
    (net (code "11") (name "CAN_RX") (class "Default")
      (node (ref "IC101") (pin "32") (pinfunction "PTE25/CAN1_RXUART4_RX_32") (pintype "bidirectional"))
      (node (ref "IC105") (pin "4") (pinfunction "RXD_4") (pintype "bidirectional"))
    )
    (net (code "12") (name "CAN_TX") (class "Default")
      (node (ref "IC101") (pin "31") (pinfunction "PTE24/CAN1_TX/UART4_TX_31") (pintype "bidirectional"))
      (node (ref "IC105") (pin "1") (pinfunction "TXD_1") (pintype "bidirectional"))
    )
    (net (code "13") (name "CLK_TMC") (class "Default")
      (node (ref "IC102") (pin "4") (pinfunction "O_4") (pintype "output"))
      (node (ref "IC201") (pin "5") (pinfunction "CLK_5") (pintype "input"))
      (node (ref "IC301") (pin "16") (pinfunction "CLK_16") (pintype "input"))
    )
    (net (code "14") (name "DIR1") (class "Default")
      (node (ref "IC301") (pin "30") (pinfunction "DIR_30") (pintype "input"))
      (node (ref "JP206") (pin "2") (pinfunction "2_2") (pintype "passive"))
    )
    (net (code "15") (name "GND") (class "Default")
      (node (ref "C101") (pin "2") (pinfunction "2_2") (pintype "passive"))
      (node (ref "C102") (pin "2") (pinfunction "2_2") (pintype "passive"))
      (node (ref "C103") (pin "2") (pinfunction "2_2") (pintype "passive"))
      (node (ref "C104") (pin "2") (pinfunction "2_2") (pintype "passive"))
      (node (ref "C105") (pin "2") (pinfunction "2_2") (pintype "passive"))
      (node (ref "C106") (pin "1") (pinfunction "1_1") (pintype "passive"))
      (node (ref "C107") (pin "1") (pinfunction "1_1") (pintype "passive"))
      (node (ref "C108") (pin "2") (pinfunction "2_2") (pintype "passive"))
      (node (ref "C109") (pin "2") (pinfunction "2_2") (pintype "passive"))
      (node (ref "C110") (pin "2") (pinfunction "2_2") (pintype "passive"))
      (node (ref "C112") (pin "2") (pinfunction "2_2") (pintype "passive"))
      (node (ref "C113") (pin "2") (pinfunction "2_2") (pintype "passive"))
      (node (ref "C114") (pin "2") (pinfunction "2_2") (pintype "passive"))
      (node (ref "C115") (pin "1") (pinfunction "1_1") (pintype "passive"))
      (node (ref "C116") (pin "1") (pinfunction "1_1") (pintype "passive"))
      (node (ref "C117") (pin "1") (pinfunction "1_1") (pintype "passive"))
      (node (ref "C118") (pin "2") (pinfunction "2_2") (pintype "passive"))
      (node (ref "C119") (pin "2") (pinfunction "2_2") (pintype "passive"))
      (node (ref "C120") (pin "2") (pinfunction "2_2") (pintype "passive"))
      (node (ref "C201") (pin "2") (pinfunction "2_2") (pintype "passive"))
      (node (ref "C202") (pin "2") (pinfunction "2_2") (pintype "passive"))
      (node (ref "C203") (pin "2") (pinfunction "2_2") (pintype "passive"))
      (node (ref "C204") (pin "2") (pinfunction "2_2") (pintype "passive"))
      (node (ref "C205") (pin "2") (pinfunction "2_2") (pintype "passive"))
      (node (ref "C206") (pin "2") (pinfunction "2_2") (pintype "passive"))
      (node (ref "C207") (pin "2") (pinfunction "2_2") (pintype "passive"))
      (node (ref "C208") (pin "2") (pinfunction "2_2") (pintype "passive"))
      (node (ref "C302") (pin "2") (pinfunction "2_2") (pintype "passive"))
      (node (ref "C303") (pin "2") (pinfunction "2_2") (pintype "passive"))
      (node (ref "C304") (pin "2") (pinfunction "2_2") (pintype "passive"))
      (node (ref "C305") (pin "-") (pinfunction "-_-") (pintype "passive"))
      (node (ref "C306") (pin "2") (pinfunction "2_2") (pintype "passive"))
      (node (ref "C307") (pin "2") (pinfunction "2_2") (pintype "passive"))
      (node (ref "C308") (pin "-") (pinfunction "-_-") (pintype "passive"))
      (node (ref "C401") (pin "2") (pinfunction "2_2") (pintype "passive"))
      (node (ref "C402") (pin "2") (pinfunction "2_2") (pintype "passive"))
      (node (ref "C405") (pin "2") (pinfunction "2_2") (pintype "passive"))
      (node (ref "C406") (pin "2") (pinfunction "2_2") (pintype "passive"))
      (node (ref "C407") (pin "2") (pinfunction "2_2") (pintype "passive"))
      (node (ref "C408") (pin "2") (pinfunction "2_2") (pintype "passive"))
      (node (ref "D101") (pin "2") (pinfunction "GND_2") (pintype "bidirectional"))
      (node (ref "IC101") (pin "17") (pinfunction "ADC1_DM1_17") (pintype "bidirectional"))
      (node (ref "IC101") (pin "19") (pinfunction "PGA0_DM/ADC0_DM0/ADC1_DM3_19") (pintype "bidirectional"))
      (node (ref "IC101") (pin "21") (pinfunction "PGA1_DM/ADC1_DM0/ADC0_DM3_21") (pintype "bidirectional"))
      (node (ref "IC101") (pin "24") (pinfunction "VREFL_24") (pintype "bidirectional"))
      (node (ref "IC101") (pin "25") (pinfunction "VSS_A_25") (pintype "bidirectional"))
      (node (ref "IC101") (pin "41") (pinfunction "VSS_41") (pintype "bidirectional"))
      (node (ref "IC101") (pin "49") (pinfunction "VSS_49") (pintype "bidirectional"))
      (node (ref "IC101") (pin "60") (pinfunction "VSS_60") (pintype "bidirectional"))
      (node (ref "IC101") (pin "74") (pinfunction "VSS_74") (pintype "bidirectional"))
      (node (ref "IC101") (pin "88") (pinfunction "VSS_88") (pintype "bidirectional"))
      (node (ref "IC101") (pin "9") (pinfunction "VSS_9") (pintype "bidirectional"))
      (node (ref "IC102") (pin "3") (pinfunction "GND_3") (pintype "power_in"))
      (node (ref "IC103") (pin "4") (pinfunction "GND_4") (pintype "bidirectional"))
      (node (ref "IC104") (pin "5") (pinfunction "GND_5") (pintype "bidirectional"))
      (node (ref "IC105") (pin "2") (pinfunction "GND_2") (pintype "bidirectional"))
      (node (ref "IC105") (pin "8") (pinfunction "S_8") (pintype "bidirectional"))
      (node (ref "IC201") (pin "23") (pinfunction "GND_23") (pintype "input"))
      (node (ref "IC201") (pin "25") (pinfunction "GND_25") (pintype "input"))
      (node (ref "IC201") (pin "4") (pinfunction "TEST_4") (pintype "input"))
      (node (ref "IC201") (pin "6") (pinfunction "GND_6") (pintype "input"))
      (node (ref "IC201") (pin "EXP") (pinfunction "DIE_PAD_EXP") (pintype "input"))
      (node (ref "IC301") (pin "1") (pinfunction "GND_1") (pintype "input"))
      (node (ref "IC301") (pin "13") (pinfunction "GND_13") (pintype "input"))
      (node (ref "IC301") (pin "28") (pinfunction "GND_28") (pintype "input"))
      (node (ref "IC301") (pin "32") (pinfunction "TST_MODE_32") (pintype "input"))
      (node (ref "IC301") (pin "EXP") (pinfunction "DIE_PAD_EXP") (pintype "input"))
      (node (ref "IC401") (pin "2") (pinfunction "GND_2") (pintype "bidirectional"))
      (node (ref "IC402") (pin "2") (pinfunction "GND_2") (pintype "bidirectional"))
      (node (ref "JP101") (pin "1") (pinfunction "1_1") (pintype "passive"))
      (node (ref "JP101") (pin "2") (pinfunction "2_2") (pintype "passive"))
      (node (ref "JP201") (pin "1") (pinfunction "1_1") (pintype "passive"))
      (node (ref "JP202") (pin "1") (pinfunction "1_1") (pintype "passive"))
      (node (ref "JP203") (pin "1") (pinfunction "1_1") (pintype "passive"))
      (node (ref "JP204") (pin "1") (pinfunction "1_1") (pintype "passive"))
      (node (ref "K301") (pin "2") (pinfunction "2_2") (pintype "passive"))
      (node (ref "K302") (pin "2") (pinfunction "2_2") (pintype "passive"))
      (node (ref "LED101") (pin "C") (pinfunction "C_C") (pintype "passive"))
      (node (ref "LED102") (pin "C") (pinfunction "C_C") (pintype "passive"))
      (node (ref "LED202") (pin "C") (pinfunction "C_C") (pintype "passive"))
      (node (ref "LED301") (pin "C") (pinfunction "C_C") (pintype "passive"))
      (node (ref "LED401") (pin "C") (pinfunction "C_C") (pintype "passive"))
      (node (ref "Q101") (pin "2") (pinfunction "S_2") (pintype "passive"))
      (node (ref "Q102") (pin "2") (pinfunction "S_2") (pintype "passive"))
      (node (ref "R105") (pin "2") (pinfunction "2_2") (pintype "passive"))
      (node (ref "R107") (pin "1") (pinfunction "1_1") (pintype "passive"))
      (node (ref "R108") (pin "1") (pinfunction "1_1") (pintype "passive"))
      (node (ref "R110") (pin "1") (pinfunction "1_1") (pintype "passive"))
      (node (ref "R112") (pin "1") (pinfunction "1_1") (pintype "passive"))
      (node (ref "R114") (pin "1") (pinfunction "1_1") (pintype "passive"))
      (node (ref "R303") (pin "1") (pinfunction "1_1") (pintype "passive"))
      (node (ref "R305") (pin "1") (pinfunction "1_1") (pintype "passive"))
      (node (ref "R402") (pin "1") (pinfunction "1_1") (pintype "passive"))
      (node (ref "SV101") (pin "5") (pinfunction "5_5") (pintype "passive"))
      (node (ref "TP5") (pin "TP") (pinfunction "TP_TP") (pintype "input"))
      (node (ref "U$401") (pin "A") (pinfunction "A_A") (pintype "bidirectional"))
      (node (ref "X101") (pin "4") (pinfunction "4_4") (pintype "passive"))
      (node (ref "X101") (pin "5") (pinfunction "5_5") (pintype "passive"))
      (node (ref "X101") (pin "M1") (pinfunction "S1_M1") (pintype "passive"))
      (node (ref "X101") (pin "M2") (pinfunction "S2_M2") (pintype "passive"))
      (node (ref "X101") (pin "M3") (pinfunction "S3_M3") (pintype "passive"))
      (node (ref "X101") (pin "M4") (pinfunction "S4_M4") (pintype "passive"))
      (node (ref "X401") (pin "1") (pinfunction "GND_1") (pintype "bidirectional"))
      (node (ref "Y101") (pin "2") (pinfunction "P$2_2") (pintype "bidirectional"))
      (node (ref "Y101") (pin "4") (pinfunction "P$4_4") (pintype "bidirectional"))
    )
    (net (code "16") (name "Net-(C101-Pad1)") (class "Default")
      (node (ref "C101") (pin "1") (pinfunction "1_1") (pintype "passive"))
      (node (ref "L102") (pin "1") (pinfunction "1_1") (pintype "passive"))
      (node (ref "X101") (pin "1") (pinfunction "1_1") (pintype "passive"))
    )
    (net (code "17") (name "Net-(D101-I04)") (class "Default")
      (node (ref "D101") (pin "6") (pinfunction "I04_6") (pintype "bidirectional"))
      (node (ref "IC101") (pin "10") (pinfunction "USB0_DP_10") (pintype "bidirectional"))
      (node (ref "R107") (pin "2") (pinfunction "2_2") (pintype "passive"))
      (node (ref "X101") (pin "3") (pinfunction "3_3") (pintype "passive"))
    )
    (net (code "18") (name "Net-(D101-IO3)") (class "Default")
      (node (ref "D101") (pin "4") (pinfunction "IO3_4") (pintype "bidirectional"))
      (node (ref "IC101") (pin "11") (pinfunction "USB0_DM_11") (pintype "bidirectional"))
      (node (ref "R108") (pin "2") (pinfunction "2_2") (pintype "passive"))
      (node (ref "X101") (pin "2") (pinfunction "2_2") (pintype "passive"))
    )
    (net (code "19") (name "Net-(IC101-ADC1_DP1)") (class "Default")
      (node (ref "C114") (pin "1") (pinfunction "1_1") (pintype "passive"))
      (node (ref "IC101") (pin "16") (pinfunction "ADC1_DP1_16") (pintype "bidirectional"))
      (node (ref "R109") (pin "1") (pinfunction "1_1") (pintype "passive"))
      (node (ref "R110") (pin "2") (pinfunction "2_2") (pintype "passive"))
    )
    (net (code "20") (name "Net-(IC101-EXTAL)") (class "Default")
      (node (ref "C106") (pin "2") (pinfunction "2_2") (pintype "passive"))
      (node (ref "IC101") (pin "50") (pinfunction "EXTAL_50") (pintype "bidirectional"))
      (node (ref "Y101") (pin "1") (pinfunction "P$1_1") (pintype "bidirectional"))
    )
    (net (code "21") (name "Net-(IC101-PGA0_DP{slash}ADC0_DP0{slash}ADC1_DP3)") (class "Default")
      (node (ref "IC101") (pin "18") (pinfunction "PGA0_DP/ADC0_DP0/ADC1_DP3_18") (pintype "bidirectional"))
      (node (ref "R111") (pin "1") (pinfunction "1_1") (pintype "passive"))
      (node (ref "R112") (pin "2") (pinfunction "2_2") (pintype "passive"))
    )
    (net (code "22") (name "Net-(IC101-PGA1_DP{slash}ADC1_DP0{slash}ADC0_DP3)") (class "Default")
      (node (ref "IC101") (pin "20") (pinfunction "PGA1_DP/ADC1_DP0/ADC0_DP3_20") (pintype "bidirectional"))
      (node (ref "R113") (pin "1") (pinfunction "1_1") (pintype "passive"))
      (node (ref "R114") (pin "2") (pinfunction "2_2") (pintype "passive"))
    )
    (net (code "23") (name "Net-(IC101-PTA1)") (class "Default")
      (node (ref "IC101") (pin "35") (pinfunction "PTA1_35") (pintype "bidirectional"))
      (node (ref "R101") (pin "1") (pinfunction "1_1") (pintype "passive"))
    )
    (net (code "24") (name "Net-(IC101-PTA2)") (class "Default")
      (node (ref "IC101") (pin "36") (pinfunction "PTA2_36") (pintype "bidirectional"))
      (node (ref "R102") (pin "1") (pinfunction "1_1") (pintype "passive"))
    )
    (net (code "25") (name "Net-(IC101-PTA4)") (class "Default")
      (node (ref "IC101") (pin "38") (pinfunction "PTA4_38") (pintype "bidirectional"))
      (node (ref "R104") (pin "2") (pinfunction "2_2") (pintype "passive"))
      (node (ref "R105") (pin "1") (pinfunction "1_1") (pintype "passive"))
    )
    (net (code "26") (name "Net-(IC101-PTC3{slash}CLKOUT{slash}SPI0_PCS1)") (class "Default")
      (node (ref "IC101") (pin "73") (pinfunction "PTC3/CLKOUT/SPI0_PCS1_73") (pintype "bidirectional"))
      (node (ref "IC102") (pin "2") (pinfunction "I_2") (pintype "input"))
    )
    (net (code "27") (name "Net-(IC101-PTC4{slash}LLWU_P8{slash}SPI0_PCS0)") (class "Default")
      (node (ref "IC101") (pin "76") (pinfunction "PTC4/LLWU_P8/SPI0_PCS0_76") (pintype "bidirectional"))
      (node (ref "IC103") (pin "1") (pinfunction "NCS_1") (pintype "bidirectional"))
    )
    (net (code "28") (name "Net-(IC101-PTC5{slash}LLWU_P9{slash}SPI0_SCK)") (class "Default")
      (node (ref "IC101") (pin "77") (pinfunction "PTC5/LLWU_P9/SPI0_SCK_77") (pintype "bidirectional"))
      (node (ref "IC103") (pin "6") (pinfunction "SCK_6") (pintype "bidirectional"))
    )
    (net (code "29") (name "Net-(IC101-PTC6{slash}LLWU_P10{slash}SPI0_SOUT)") (class "Default")
      (node (ref "IC101") (pin "78") (pinfunction "PTC6/LLWU_P10/SPI0_SOUT_78") (pintype "bidirectional"))
      (node (ref "IC103") (pin "5") (pinfunction "SI_5") (pintype "bidirectional"))
    )
    (net (code "30") (name "Net-(IC101-PTC7{slash}SPI0_SIN)") (class "Default")
      (node (ref "IC101") (pin "79") (pinfunction "PTC7/SPI0_SIN_79") (pintype "bidirectional"))
      (node (ref "IC103") (pin "2") (pinfunction "SO_2") (pintype "bidirectional"))
    )
    (net (code "31") (name "Net-(IC101-VBAT)") (class "Default")
      (node (ref "C113") (pin "1") (pinfunction "1_1") (pintype "passive"))
      (node (ref "IC101") (pin "30") (pinfunction "VBAT_30") (pintype "bidirectional"))
    )
    (net (code "32") (name "Net-(IC101-VDD_A)") (class "Default")
      (node (ref "C109") (pin "1") (pinfunction "1_1") (pintype "passive"))
      (node (ref "C112") (pin "1") (pinfunction "1_1") (pintype "passive"))
      (node (ref "IC101") (pin "22") (pinfunction "VDD_A_22") (pintype "bidirectional"))
      (node (ref "IC101") (pin "23") (pinfunction "VREFH_23") (pintype "bidirectional"))
      (node (ref "L101") (pin "2") (pinfunction "2_2") (pintype "passive"))
    )
    (net (code "33") (name "Net-(IC101-VOUT33)") (class "Default")
      (node (ref "C120") (pin "1") (pinfunction "1_1") (pintype "passive"))
      (node (ref "IC101") (pin "12") (pinfunction "VOUT33_12") (pintype "bidirectional"))
    )
    (net (code "34") (name "Net-(IC101-XTAL)") (class "Default")
      (node (ref "C107") (pin "2") (pinfunction "2_2") (pintype "passive"))
      (node (ref "IC101") (pin "51") (pinfunction "XTAL_51") (pintype "bidirectional"))
      (node (ref "Y101") (pin "3") (pinfunction "P$3_3") (pintype "bidirectional"))
    )
    (net (code "35") (name "Net-(IC201-REF1)") (class "Default")
      (node (ref "C206") (pin "1") (pinfunction "1_1") (pintype "passive"))
      (node (ref "IC201") (pin "31") (pinfunction "REF1_31") (pintype "input"))
      (node (ref "JP201") (pin "2") (pinfunction "2_2") (pintype "passive"))
      (node (ref "R201") (pin "P$3") (pinfunction "1_P$3") (pintype "bidirectional"))
    )
    (net (code "36") (name "Net-(IC201-REF2)") (class "Default")
      (node (ref "C204") (pin "1") (pinfunction "1_1") (pintype "passive"))
      (node (ref "IC201") (pin "1") (pinfunction "REF2_1") (pintype "input"))
      (node (ref "JP201") (pin "4") (pinfunction "4_4") (pintype "passive"))
      (node (ref "R201") (pin "P$2") (pinfunction "1_P$2") (pintype "bidirectional"))
    )
    (net (code "37") (name "Net-(IC201-REF3)") (class "Default")
      (node (ref "C202") (pin "1") (pinfunction "1_1") (pintype "passive"))
      (node (ref "IC201") (pin "2") (pinfunction "REF3_2") (pintype "input"))
      (node (ref "JP201") (pin "6") (pinfunction "6_6") (pintype "passive"))
      (node (ref "R201") (pin "P$1") (pinfunction "1_P$1") (pintype "bidirectional"))
    )
    (net (code "38") (name "Net-(IC201-REFR1)") (class "Default")
      (node (ref "C205") (pin "1") (pinfunction "1_1") (pintype "passive"))
      (node (ref "IC201") (pin "28") (pinfunction "REFR1_28") (pintype "input"))
      (node (ref "JP201") (pin "3") (pinfunction "3_3") (pintype "passive"))
      (node (ref "R203") (pin "P$2") (pinfunction "1_P$2") (pintype "bidirectional"))
    )
    (net (code "39") (name "Net-(IC201-REFR2)") (class "Default")
      (node (ref "C203") (pin "1") (pinfunction "1_1") (pintype "passive"))
      (node (ref "IC201") (pin "13") (pinfunction "REFR2_13") (pintype "input"))
      (node (ref "JP201") (pin "5") (pinfunction "5_5") (pintype "passive"))
      (node (ref "R203") (pin "P$4") (pinfunction "1_P$4") (pintype "bidirectional"))
    )
    (net (code "40") (name "Net-(IC201-REFR3)") (class "Default")
      (node (ref "C201") (pin "1") (pinfunction "1_1") (pintype "passive"))
      (node (ref "IC201") (pin "29") (pinfunction "REFR3_29") (pintype "input"))
      (node (ref "JP201") (pin "7") (pinfunction "7_7") (pintype "passive"))
      (node (ref "R203") (pin "P$1") (pinfunction "1_P$1") (pintype "bidirectional"))
    )
    (net (code "41") (name "Net-(IC201-SCK_S_D1)") (class "Default")
      (node (ref "IC201") (pin "17") (pinfunction "SCK_S_D1_17") (pintype "output"))
      (node (ref "JP206") (pin "3") (pinfunction "3_3") (pintype "passive"))
    )
    (net (code "42") (name "Net-(IC201-SDI_S_D2)") (class "Default")
      (node (ref "IC201") (pin "27") (pinfunction "SDI_S_D2_27") (pintype "bidirectional"))
      (node (ref "JP204") (pin "3") (pinfunction "3_3") (pintype "passive"))
    )
    (net (code "43") (name "Net-(IC201-SDO_S_S1)") (class "Default")
      (node (ref "IC201") (pin "15") (pinfunction "SDO_S_S1_15") (pintype "output"))
      (node (ref "JP205") (pin "3") (pinfunction "3_3") (pintype "passive"))
    )
    (net (code "44") (name "Net-(IC201-V33)") (class "Default")
      (node (ref "C207") (pin "1") (pinfunction "1_1") (pintype "passive"))
      (node (ref "IC201") (pin "22") (pinfunction "V33_22") (pintype "input"))
    )
    (net (code "45") (name "Net-(IC201-~{SCS2_S3})") (class "Default")
      (node (ref "IC201") (pin "19") (pinfunction "~{SCS2_S3}_19") (pintype "output"))
      (node (ref "JP202") (pin "2") (pinfunction "2_2") (pintype "passive"))
    )
    (net (code "46") (name "Net-(IC201-~{SCS3_D3})") (class "Default")
      (node (ref "IC201") (pin "20") (pinfunction "~{SCS3_D3}_20") (pintype "output"))
      (node (ref "JP202") (pin "3") (pinfunction "3_3") (pintype "passive"))
    )
    (net (code "47") (name "Net-(IC201-~{SCS_S_S2})") (class "Default")
      (node (ref "IC201") (pin "18") (pinfunction "~{SCS_S_S2}_18") (pintype "output"))
      (node (ref "JP204") (pin "2") (pinfunction "2_2") (pintype "passive"))
    )
    (net (code "48") (name "Net-(IC301-5VOUT)") (class "Default")
      (node (ref "C303") (pin "1") (pinfunction "1_1") (pintype "passive"))
      (node (ref "IC301") (pin "9") (pinfunction "5VOUT_9") (pintype "output"))
    )
    (net (code "49") (name "Net-(IC301-HA1)") (class "Default")
      (node (ref "IC301") (pin "2") (pinfunction "HA1_2") (pintype "output"))
      (node (ref "T301") (pin "5") (pinfunction "G_P_5") (pintype "bidirectional"))
    )
    (net (code "50") (name "Net-(IC301-HA2)") (class "Default")
      (node (ref "IC301") (pin "3") (pinfunction "HA2_3") (pintype "output"))
      (node (ref "T302") (pin "5") (pinfunction "G_P_5") (pintype "bidirectional"))
    )
    (net (code "51") (name "Net-(IC301-HB1)") (class "Default")
      (node (ref "IC301") (pin "23") (pinfunction "HB1_23") (pintype "output"))
      (node (ref "T303") (pin "5") (pinfunction "G_P_5") (pintype "bidirectional"))
    )
    (net (code "52") (name "Net-(IC301-HB2)") (class "Default")
      (node (ref "IC301") (pin "22") (pinfunction "HB2_22") (pintype "output"))
      (node (ref "T304") (pin "5") (pinfunction "G_P_5") (pintype "bidirectional"))
    )
    (net (code "53") (name "Net-(IC301-LA1)") (class "Default")
      (node (ref "IC301") (pin "6") (pinfunction "LA1_6") (pintype "output"))
      (node (ref "T301") (pin "2") (pinfunction "G_N_2") (pintype "bidirectional"))
    )
    (net (code "54") (name "Net-(IC301-LA2)") (class "Default")
      (node (ref "IC301") (pin "7") (pinfunction "LA2_7") (pintype "output"))
      (node (ref "T302") (pin "2") (pinfunction "G_N_2") (pintype "bidirectional"))
    )
    (net (code "55") (name "Net-(IC301-LB1)") (class "Default")
      (node (ref "IC301") (pin "19") (pinfunction "LB1_19") (pintype "output"))
      (node (ref "T303") (pin "2") (pinfunction "G_N_2") (pintype "bidirectional"))
    )
    (net (code "56") (name "Net-(IC301-LB2)") (class "Default")
      (node (ref "IC301") (pin "18") (pinfunction "LB2_18") (pintype "output"))
      (node (ref "T304") (pin "2") (pinfunction "G_N_2") (pintype "bidirectional"))
    )
    (net (code "57") (name "Net-(IC301-VCC_IO)") (class "Default")
      (node (ref "C304") (pin "1") (pinfunction "1_1") (pintype "passive"))
      (node (ref "IC301") (pin "29") (pinfunction "VCC_IO_29") (pintype "input"))
      (node (ref "R302") (pin "1") (pinfunction "1_1") (pintype "passive"))
    )
    (net (code "58") (name "Net-(IC301-VHS)") (class "Default")
      (node (ref "C301") (pin "2") (pinfunction "2_2") (pintype "passive"))
      (node (ref "IC301") (pin "24") (pinfunction "VHS_24") (pintype "input"))
    )
    (net (code "59") (name "Net-(IC401-CB)") (class "Default")
      (node (ref "C403") (pin "1") (pinfunction "1_1") (pintype "passive"))
      (node (ref "C404") (pin "1") (pinfunction "1_1") (pintype "passive"))
      (node (ref "IC401") (pin "1") (pinfunction "CB_1") (pintype "bidirectional"))
    )
    (net (code "60") (name "Net-(IC401-FB)") (class "Default")
      (node (ref "IC401") (pin "3") (pinfunction "FB_3") (pintype "bidirectional"))
      (node (ref "R402") (pin "2") (pinfunction "2_2") (pintype "passive"))
      (node (ref "R403") (pin "1") (pinfunction "1_1") (pintype "passive"))
    )
    (net (code "61") (name "Net-(IC401-SW)") (class "Default")
      (node (ref "C403") (pin "2") (pinfunction "2_2") (pintype "passive"))
      (node (ref "C404") (pin "2") (pinfunction "2_2") (pintype "passive"))
      (node (ref "IC401") (pin "6") (pinfunction "SW_6") (pintype "bidirectional"))
      (node (ref "L402") (pin "1") (pinfunction "1_1") (pintype "passive"))
      (node (ref "U$401") (pin "C") (pinfunction "C_C") (pintype "bidirectional"))
    )
    (net (code "62") (name "Net-(IC401-VIN)") (class "Default")
      (node (ref "C402") (pin "1") (pinfunction "1_1") (pintype "passive"))
      (node (ref "IC401") (pin "4") (pinfunction "~{SHDN}_4") (pintype "bidirectional"))
      (node (ref "IC401") (pin "5") (pinfunction "VIN_5") (pintype "bidirectional"))
      (node (ref "L401") (pin "2") (pinfunction "2_2") (pintype "passive"))
    )
    (net (code "63") (name "Net-(JP203-Pad2)") (class "Default")
      (node (ref "JP203") (pin "2") (pinfunction "2_2") (pintype "passive"))
      (node (ref "JP205") (pin "1") (pinfunction "1_1") (pintype "passive"))
    )
    (net (code "64") (name "Net-(JP203-Pad3)") (class "Default")
      (node (ref "JP203") (pin "3") (pinfunction "3_3") (pintype "passive"))
      (node (ref "JP206") (pin "1") (pinfunction "1_1") (pintype "passive"))
    )
    (net (code "65") (name "Net-(K301-Pad1)") (class "Default")
      (node (ref "K301") (pin "1") (pinfunction "1_1") (pintype "passive"))
      (node (ref "R304") (pin "1") (pinfunction "1_1") (pintype "passive"))
    )
    (net (code "66") (name "Net-(K302-Pad1)") (class "Default")
      (node (ref "K302") (pin "1") (pinfunction "1_1") (pintype "passive"))
      (node (ref "R306") (pin "1") (pinfunction "1_1") (pintype "passive"))
    )
    (net (code "67") (name "Net-(LED101-PadA)") (class "Default")
      (node (ref "LED101") (pin "A") (pinfunction "A_A") (pintype "passive"))
      (node (ref "R101") (pin "2") (pinfunction "2_2") (pintype "passive"))
    )
    (net (code "68") (name "Net-(LED102-PadA)") (class "Default")
      (node (ref "LED102") (pin "A") (pinfunction "A_A") (pintype "passive"))
      (node (ref "R102") (pin "2") (pinfunction "2_2") (pintype "passive"))
    )
    (net (code "69") (name "Net-(LED201-PadA)") (class "Default")
      (node (ref "LED201") (pin "A") (pinfunction "A_A") (pintype "passive"))
      (node (ref "R202") (pin "1") (pinfunction "1_1") (pintype "passive"))
    )
    (net (code "70") (name "Net-(LED202-PadA)") (class "Default")
      (node (ref "LED202") (pin "A") (pinfunction "A_A") (pintype "passive"))
      (node (ref "R204") (pin "2") (pinfunction "2_2") (pintype "passive"))
    )
    (net (code "71") (name "Net-(LED301-PadA)") (class "Default")
      (node (ref "LED301") (pin "A") (pinfunction "A_A") (pintype "passive"))
      (node (ref "R301") (pin "2") (pinfunction "2_2") (pintype "passive"))
    )
    (net (code "72") (name "Net-(LED401-PadA)") (class "Default")
      (node (ref "LED401") (pin "A") (pinfunction "A_A") (pintype "passive"))
      (node (ref "R401") (pin "2") (pinfunction "2_2") (pintype "passive"))
    )
    (net (code "73") (name "Net-(Q101-D)") (class "Default")
      (node (ref "JP101") (pin "11") (pinfunction "11_11") (pintype "passive"))
      (node (ref "Q101") (pin "3") (pinfunction "D_3") (pintype "passive"))
    )
    (net (code "74") (name "Net-(Q102-D)") (class "Default")
      (node (ref "JP101") (pin "13") (pinfunction "13_13") (pintype "passive"))
      (node (ref "Q102") (pin "3") (pinfunction "D_3") (pintype "passive"))
    )
    (net (code "75") (name "OPENDRAIN_1") (class "Default")
      (node (ref "IC101") (pin "90") (pinfunction "PTC16_90") (pintype "bidirectional"))
      (node (ref "Q101") (pin "1") (pinfunction "G_1") (pintype "passive"))
    )
    (net (code "76") (name "OPENDRAIN_2") (class "Default")
      (node (ref "IC101") (pin "91") (pinfunction "PTC17_91") (pintype "bidirectional"))
      (node (ref "Q102") (pin "1") (pinfunction "G_1") (pintype "passive"))
    )
    (net (code "77") (name "PHASE_A") (class "Default")
      (node (ref "IC101") (pin "64") (pinfunction "PTB18/FTM2_CH0/CAN0_TX_64") (pintype "bidirectional"))
      (node (ref "JP101") (pin "10") (pinfunction "10_10") (pintype "passive"))
      (node (ref "R106") (pin "P$3") (pinfunction "1_P$3") (pintype "bidirectional"))
    )
    (net (code "78") (name "PHASE_B") (class "Default")
      (node (ref "IC101") (pin "65") (pinfunction "PTB19/FTM2_CH1/CAN0_RX_65") (pintype "bidirectional"))
      (node (ref "JP101") (pin "12") (pinfunction "12_12") (pintype "passive"))
      (node (ref "R106") (pin "P$2") (pinfunction "1_P$2") (pintype "bidirectional"))
    )
    (net (code "79") (name "PHASE_Z") (class "Default")
      (node (ref "IC101") (pin "80") (pinfunction "PTC8/ADC1_SE4B_80") (pintype "bidirectional"))
      (node (ref "JP101") (pin "14") (pinfunction "14_14") (pintype "passive"))
      (node (ref "R106") (pin "P$4") (pinfunction "1_P$4") (pintype "bidirectional"))
    )
    (net (code "80") (name "POSCOMP") (class "Default")
      (node (ref "IC101") (pin "54") (pinfunction "PTB1/FTM1_CH0/ADC[0/1]_SE9_54") (pintype "bidirectional"))
      (node (ref "IC201") (pin "30") (pinfunction "POSCMP_30") (pintype "bidirectional"))
      (node (ref "R204") (pin "1") (pinfunction "1_1") (pintype "passive"))
    )
    (net (code "81") (name "PWM_D0") (class "Default")
      (node (ref "IC101") (pin "71") (pinfunction "PTC1/FTM0_CH0_71") (pintype "bidirectional"))
      (node (ref "JP101") (pin "3") (pinfunction "3_3") (pintype "passive"))
    )
    (net (code "82") (name "PWM_D1") (class "Default")
      (node (ref "IC101") (pin "72") (pinfunction "PTC2/FTM0_CH1_72") (pintype "bidirectional"))
      (node (ref "JP101") (pin "5") (pinfunction "5_5") (pintype "passive"))
    )
    (net (code "83") (name "PWM_D2") (class "Default")
      (node (ref "IC101") (pin "97") (pinfunction "PTD4/FTM0_CH4_97") (pintype "bidirectional"))
      (node (ref "JP101") (pin "7") (pinfunction "7_7") (pintype "passive"))
    )
    (net (code "84") (name "PWM_U0") (class "Default")
      (node (ref "IC101") (pin "98") (pinfunction "PTD5/FTM0_CH5_98") (pintype "bidirectional"))
      (node (ref "JP101") (pin "4") (pinfunction "4_4") (pintype "passive"))
    )
    (net (code "85") (name "PWM_U1") (class "Default")
      (node (ref "IC101") (pin "99") (pinfunction "PTD6/FTM0_CH6_99") (pintype "bidirectional"))
      (node (ref "JP101") (pin "6") (pinfunction "6_6") (pintype "passive"))
    )
    (net (code "86") (name "PWM_U2") (class "Default")
      (node (ref "IC101") (pin "100") (pinfunction "PTD7/FTM0_CH7_100") (pintype "bidirectional"))
      (node (ref "JP101") (pin "8") (pinfunction "8_8") (pintype "passive"))
    )
    (net (code "87") (name "RESET") (class "Default")
      (node (ref "IC101") (pin "52") (pinfunction "RESET_B_52") (pintype "bidirectional"))
      (node (ref "R103") (pin "P$2") (pinfunction "1_P$2") (pintype "bidirectional"))
      (node (ref "TP3") (pin "TP") (pinfunction "TP_TP") (pintype "input"))
    )
    (net (code "88") (name "RS485+") (class "Default")
      (node (ref "IC104") (pin "6") (pinfunction "+_6") (pintype "bidirectional"))
      (node (ref "SV101") (pin "6") (pinfunction "6_6") (pintype "passive"))
    )
    (net (code "89") (name "RS485-") (class "Default")
      (node (ref "IC104") (pin "7") (pinfunction "-_7") (pintype "bidirectional"))
      (node (ref "SV101") (pin "7") (pinfunction "7_7") (pintype "passive"))
    )
    (net (code "90") (name "RS485_DIR") (class "Default")
      (node (ref "IC101") (pin "47") (pinfunction "PTA17/UART0_RTS_47") (pintype "bidirectional"))
      (node (ref "IC104") (pin "2") (pinfunction "NRE_2") (pintype "bidirectional"))
      (node (ref "IC104") (pin "3") (pinfunction "DE_3") (pintype "bidirectional"))
    )
    (net (code "91") (name "RS485_RX") (class "Default")
      (node (ref "IC101") (pin "45") (pinfunction "PTA15/UART0_RX_45") (pintype "bidirectional"))
      (node (ref "IC104") (pin "1") (pinfunction "R_1") (pintype "bidirectional"))
      (node (ref "SV101") (pin "10") (pinfunction "10_10") (pintype "passive"))
    )
    (net (code "92") (name "RS485_TX") (class "Default")
      (node (ref "IC101") (pin "44") (pinfunction "PTA14/UART0_TX_44") (pintype "bidirectional"))
      (node (ref "IC104") (pin "4") (pinfunction "D_4") (pintype "bidirectional"))
      (node (ref "SV101") (pin "9") (pinfunction "9_9") (pintype "passive"))
    )
    (net (code "93") (name "SG_TST") (class "Default")
      (node (ref "IC101") (pin "43") (pinfunction "PTA13/FTM1_CH1_43") (pintype "bidirectional"))
      (node (ref "IC301") (pin "27") (pinfunction "SG_TST_27") (pintype "output"))
      (node (ref "R301") (pin "1") (pinfunction "1_1") (pintype "passive"))
    )
    (net (code "94") (name "SPI1_MISO") (class "Default")
      (node (ref "IC101") (pin "63") (pinfunction "PTB17/SPI1_SIN_63") (pintype "bidirectional"))
      (node (ref "IC201") (pin "12") (pinfunction "SDOZ_C_12") (pintype "tri_state"))
      (node (ref "IC301") (pin "10") (pinfunction "SDO_10") (pintype "tri_state"))
    )
    (net (code "95") (name "SPI1_MOSI") (class "Default")
      (node (ref "IC101") (pin "62") (pinfunction "PTB16/SPI1_SOUT_62") (pintype "bidirectional"))
      (node (ref "IC201") (pin "10") (pinfunction "SDI_C_10") (pintype "input"))
      (node (ref "IC301") (pin "11") (pinfunction "SDI_11") (pintype "input"))
    )
    (net (code "96") (name "SPI1_SCK") (class "Default")
      (node (ref "IC101") (pin "59") (pinfunction "PTB11/SPI1_SCK_59") (pintype "bidirectional"))
      (node (ref "IC201") (pin "8") (pinfunction "SCK_C_8") (pintype "input"))
      (node (ref "IC301") (pin "12") (pinfunction "SCK_12") (pintype "input"))
    )
    (net (code "97") (name "SRA") (class "Default")
      (node (ref "IC301") (pin "8") (pinfunction "SRA_8") (pintype "input"))
      (node (ref "R303") (pin "2") (pinfunction "2_2") (pintype "passive"))
      (node (ref "R304") (pin "2") (pinfunction "2_2") (pintype "passive"))
      (node (ref "T301") (pin "1") (pinfunction "S_N_1") (pintype "bidirectional"))
      (node (ref "T302") (pin "1") (pinfunction "S_N_1") (pintype "bidirectional"))
    )
    (net (code "98") (name "SRB") (class "Default")
      (node (ref "IC301") (pin "17") (pinfunction "SRB_17") (pintype "input"))
      (node (ref "R305") (pin "2") (pinfunction "2_2") (pintype "passive"))
      (node (ref "R306") (pin "2") (pinfunction "2_2") (pintype "passive"))
      (node (ref "T303") (pin "1") (pinfunction "S_N_1") (pintype "bidirectional"))
      (node (ref "T304") (pin "1") (pinfunction "S_N_1") (pintype "bidirectional"))
    )
    (net (code "99") (name "STEP1") (class "Default")
      (node (ref "IC301") (pin "31") (pinfunction "STEP_31") (pintype "input"))
      (node (ref "JP205") (pin "2") (pinfunction "2_2") (pintype "passive"))
    )
    (net (code "100") (name "SWCLK") (class "Default")
      (node (ref "IC101") (pin "34") (pinfunction "PTA0/SWD_CLK_34") (pintype "bidirectional"))
      (node (ref "R103") (pin "P$3") (pinfunction "1_P$3") (pintype "bidirectional"))
      (node (ref "TP1") (pin "TP") (pinfunction "TP_TP") (pintype "input"))
    )
    (net (code "101") (name "SWDIO") (class "Default")
      (node (ref "IC101") (pin "37") (pinfunction "PTA3/SWD_IO_37") (pintype "bidirectional"))
      (node (ref "R103") (pin "P$4") (pinfunction "1_P$4") (pintype "bidirectional"))
      (node (ref "TP2") (pin "TP") (pinfunction "TP_TP") (pintype "input"))
    )
    (net (code "102") (name "USB_VBUS") (class "Default")
      (node (ref "C119") (pin "1") (pinfunction "1_1") (pintype "passive"))
      (node (ref "D101") (pin "5") (pinfunction "VCC_5") (pintype "bidirectional"))
      (node (ref "D401") (pin "2") (pinfunction "A2_2") (pintype "passive"))
      (node (ref "IC101") (pin "13") (pinfunction "VREGIN_13") (pintype "bidirectional"))
      (node (ref "L102") (pin "2") (pinfunction "2_2") (pintype "passive"))
      (node (ref "R104") (pin "1") (pinfunction "1_1") (pintype "passive"))
    )
    (net (code "103") (name "V+") (class "Default")
      (node (ref "C301") (pin "1") (pinfunction "1_1") (pintype "passive"))
      (node (ref "C302") (pin "1") (pinfunction "1_1") (pintype "passive"))
      (node (ref "C305") (pin "+") (pinfunction "+_+") (pintype "passive"))
      (node (ref "C306") (pin "1") (pinfunction "1_1") (pintype "passive"))
      (node (ref "C307") (pin "1") (pinfunction "1_1") (pintype "passive"))
      (node (ref "C308") (pin "+") (pinfunction "+_+") (pintype "passive"))
      (node (ref "C401") (pin "1") (pinfunction "1_1") (pintype "passive"))
      (node (ref "IC301") (pin "25") (pinfunction "VS_25") (pintype "input"))
      (node (ref "L401") (pin "1") (pinfunction "1_1") (pintype "passive"))
      (node (ref "R113") (pin "2") (pinfunction "2_2") (pintype "passive"))
      (node (ref "T301") (pin "4") (pinfunction "S_P_4") (pintype "bidirectional"))
      (node (ref "T302") (pin "4") (pinfunction "S_P_4") (pintype "bidirectional"))
      (node (ref "T303") (pin "4") (pinfunction "S_P_4") (pintype "bidirectional"))
      (node (ref "T304") (pin "4") (pinfunction "S_P_4") (pintype "bidirectional"))
      (node (ref "X401") (pin "2") (pinfunction "V+_2") (pintype "bidirectional"))
    )
    (net (code "104") (name "unconnected-(D101-IO1-Pad1)") (class "Default")
      (node (ref "D101") (pin "1") (pinfunction "IO1_1") (pintype "bidirectional"))
    )
    (net (code "105") (name "unconnected-(D101-IO2-Pad3)") (class "Default")
      (node (ref "D101") (pin "3") (pinfunction "IO2_3") (pintype "bidirectional"))
    )
    (net (code "106") (name "unconnected-(IC101-ADC0_DM1-Pad15)") (class "Default")
      (node (ref "IC101") (pin "15") (pinfunction "ADC0_DM1_15") (pintype "bidirectional"))
    )
    (net (code "107") (name "unconnected-(IC101-ADC0_DP1-Pad14)") (class "Default")
      (node (ref "IC101") (pin "14") (pinfunction "ADC0_DP1_14") (pintype "bidirectional"))
    )
    (net (code "108") (name "unconnected-(IC101-PTA5-Pad39)") (class "Default")
      (node (ref "IC101") (pin "39") (pinfunction "PTA5_39") (pintype "bidirectional"))
    )
    (net (code "109") (name "unconnected-(IC101-PTA12{slash}FTM1_CH0-Pad42)") (class "Default")
      (node (ref "IC101") (pin "42") (pinfunction "PTA12/FTM1_CH0_42") (pintype "bidirectional"))
    )
    (net (code "110") (name "unconnected-(IC101-PTA16{slash}UART0_CTS-Pad46)") (class "Default")
      (node (ref "IC101") (pin "46") (pinfunction "PTA16/UART0_CTS_46") (pintype "bidirectional"))
    )
    (net (code "111") (name "unconnected-(IC101-PTB3{slash}ADC0_SE13-Pad56)") (class "Default")
      (node (ref "IC101") (pin "56") (pinfunction "PTB3/ADC0_SE13_56") (pintype "bidirectional"))
    )
    (net (code "112") (name "unconnected-(IC101-PTB20{slash}SPI2_PCS0-Pad66)") (class "Default")
      (node (ref "IC101") (pin "66") (pinfunction "PTB20/SPI2_PCS0_66") (pintype "bidirectional"))
    )
    (net (code "113") (name "unconnected-(IC101-PTB21{slash}SPI2_SCK-Pad67)") (class "Default")
      (node (ref "IC101") (pin "67") (pinfunction "PTB21/SPI2_SCK_67") (pintype "bidirectional"))
    )
    (net (code "114") (name "unconnected-(IC101-PTB22{slash}SPI2_SOUT-Pad68)") (class "Default")
      (node (ref "IC101") (pin "68") (pinfunction "PTB22/SPI2_SOUT_68") (pintype "bidirectional"))
    )
    (net (code "115") (name "unconnected-(IC101-PTB23{slash}SPI_SIN-Pad69)") (class "Default")
      (node (ref "IC101") (pin "69") (pinfunction "PTB23/SPI_SIN_69") (pintype "bidirectional"))
    )
    (net (code "116") (name "unconnected-(IC101-PTC0{slash}SPI0_PCS4-Pad70)") (class "Default")
      (node (ref "IC101") (pin "70") (pinfunction "PTC0/SPI0_PCS4_70") (pintype "bidirectional"))
    )
    (net (code "117") (name "unconnected-(IC101-PTC10{slash}I2C1_SCL-Pad82)") (class "Default")
      (node (ref "IC101") (pin "82") (pinfunction "PTC10/I2C1_SCL_82") (pintype "bidirectional"))
    )
    (net (code "118") (name "unconnected-(IC101-PTC11{slash}LLWU_P11{slash}I2C1_SDA-Pad83)") (class "Default")
      (node (ref "IC101") (pin "83") (pinfunction "PTC11/LLWU_P11/I2C1_SDA_83") (pintype "bidirectional"))
    )
    (net (code "119") (name "unconnected-(IC101-PTC15-Pad87)") (class "Default")
      (node (ref "IC101") (pin "87") (pinfunction "PTC15_87") (pintype "bidirectional"))
    )
    (net (code "120") (name "unconnected-(IC101-PTC18-Pad92)") (class "Default")
      (node (ref "IC101") (pin "92") (pinfunction "PTC18_92") (pintype "bidirectional"))
    )
    (net (code "121") (name "unconnected-(IC101-PTD0-Pad93)") (class "Default")
      (node (ref "IC101") (pin "93") (pinfunction "PTD0_93") (pintype "bidirectional"))
    )
    (net (code "122") (name "unconnected-(IC101-PTD1-Pad94)") (class "Default")
      (node (ref "IC101") (pin "94") (pinfunction "PTD1_94") (pintype "bidirectional"))
    )
    (net (code "123") (name "unconnected-(IC101-PTD2-Pad95)") (class "Default")
      (node (ref "IC101") (pin "95") (pinfunction "PTD2_95") (pintype "bidirectional"))
    )
    (net (code "124") (name "unconnected-(IC101-PTD3-Pad96)") (class "Default")
      (node (ref "IC101") (pin "96") (pinfunction "PTD3_96") (pintype "bidirectional"))
    )
    (net (code "125") (name "unconnected-(IC101-PTE0-Pad1)") (class "Default")
      (node (ref "IC101") (pin "1") (pinfunction "PTE0_1") (pintype "bidirectional"))
    )
    (net (code "126") (name "unconnected-(IC101-PTE1{slash}LLWU_P0-Pad2)") (class "Default")
      (node (ref "IC101") (pin "2") (pinfunction "PTE1/LLWU_P0_2") (pintype "bidirectional"))
    )
    (net (code "127") (name "unconnected-(IC101-PTE2{slash}LLWU_P1-Pad3)") (class "Default")
      (node (ref "IC101") (pin "3") (pinfunction "PTE2/LLWU_P1_3") (pintype "bidirectional"))
    )
    (net (code "128") (name "unconnected-(IC101-PTE3-Pad4)") (class "Default")
      (node (ref "IC101") (pin "4") (pinfunction "PTE3_4") (pintype "bidirectional"))
    )
    (net (code "129") (name "unconnected-(IC101-PTE4{slash}LLWU_P2-Pad5)") (class "Default")
      (node (ref "IC101") (pin "5") (pinfunction "PTE4/LLWU_P2_5") (pintype "bidirectional"))
    )
    (net (code "130") (name "unconnected-(IC101-PTE5-Pad6)") (class "Default")
      (node (ref "IC101") (pin "6") (pinfunction "PTE5_6") (pintype "bidirectional"))
    )
    (net (code "131") (name "unconnected-(IC101-PTE6{slash}SPI1_PCS3-Pad7)") (class "Default")
      (node (ref "IC101") (pin "7") (pinfunction "PTE6/SPI1_PCS3_7") (pintype "bidirectional"))
    )
    (net (code "132") (name "unconnected-(IC101-PTE26-Pad33)") (class "Default")
      (node (ref "IC101") (pin "33") (pinfunction "PTE26_33") (pintype "bidirectional"))
    )
    (net (code "133") (name "unconnected-(IC105-VREF-Pad5)") (class "Default")
      (node (ref "IC105") (pin "5") (pinfunction "VREF_5") (pintype "bidirectional"))
    )
    (net (code "134") (name "unconnected-(IC201-NC-Pad9)") (class "Default")
      (node (ref "IC201") (pin "9") (pinfunction "NC_9") (pintype "no_connect"))
    )
    (net (code "135") (name "unconnected-(IC201-NC-Pad11)") (class "Default")
      (node (ref "IC201") (pin "11") (pinfunction "NC_11") (pintype "no_connect"))
    )
    (net (code "136") (name "unconnected-(IC201-NC-Pad16)") (class "Default")
      (node (ref "IC201") (pin "16") (pinfunction "NC_16") (pintype "no_connect"))
    )
    (net (code "137") (name "unconnected-(IC201-NC-Pad24)") (class "Default")
      (node (ref "IC201") (pin "24") (pinfunction "NC_24") (pintype "no_connect"))
    )
    (net (code "138") (name "unconnected-(IC201-NC-Pad26)") (class "Default")
      (node (ref "IC201") (pin "26") (pinfunction "NC_26") (pintype "no_connect"))
    )
    (net (code "139") (name "unconnected-(IC201-NC-Pad32)") (class "Default")
      (node (ref "IC201") (pin "32") (pinfunction "NC_32") (pintype "no_connect"))
    )
    (net (code "140") (name "unconnected-(IC301-TST_ANA-Pad26)") (class "Default")
      (node (ref "IC301") (pin "26") (pinfunction "TST_ANA_26") (pintype "output"))
    )
    (net (code "141") (name "unconnected-(IC402-BYPASS-Pad4)") (class "Default")
      (node (ref "IC402") (pin "4") (pinfunction "BYPASS_4") (pintype "bidirectional"))
    )
    (net (code "142") (name "unconnected-(R103A-1-PadP$1)") (class "Default")
      (node (ref "R103") (pin "P$1") (pinfunction "1_P$1") (pintype "bidirectional"))
    )
    (net (code "143") (name "unconnected-(R103A-2-PadP$8)") (class "Default")
      (node (ref "R103") (pin "P$8") (pinfunction "2_P$8") (pintype "bidirectional"))
    )
    (net (code "144") (name "unconnected-(R201D-1-PadP$4)") (class "Default")
      (node (ref "R201") (pin "P$4") (pinfunction "1_P$4") (pintype "bidirectional"))
    )
    (net (code "145") (name "unconnected-(R203C-1-PadP$3)") (class "Default")
      (node (ref "R203") (pin "P$3") (pinfunction "1_P$3") (pintype "bidirectional"))
    )
    (net (code "146") (name "unconnected-(SV101-Pad1)") (class "Default")
      (node (ref "SV101") (pin "1") (pinfunction "1_1") (pintype "passive"))
    )
    (net (code "147") (name "unconnected-(SV101-Pad2)") (class "Default")
      (node (ref "SV101") (pin "2") (pinfunction "2_2") (pintype "passive"))
    )
    (net (code "148") (name "unconnected-(SV101-Pad8)") (class "Default")
      (node (ref "SV101") (pin "8") (pinfunction "8_8") (pintype "passive"))
    )
    (net (code "149") (name "~{CS_262}") (class "Default")
      (node (ref "IC101") (pin "57") (pinfunction "PTB9/SPI1_PCS1_57") (pintype "bidirectional"))
      (node (ref "IC301") (pin "14") (pinfunction "~{CS}_14") (pintype "input"))
    )
    (net (code "150") (name "~{EN_262}") (class "Default")
      (node (ref "IC101") (pin "55") (pinfunction "PTB2/ADC0_SE12_55") (pintype "bidirectional"))
      (node (ref "IC301") (pin "15") (pinfunction "~{EN}_15") (pintype "input"))
    )
    (net (code "151") (name "~{INT_429}") (class "Default")
      (node (ref "IC101") (pin "53") (pinfunction "PTB0/FTM1_CH0/ADC[0/1]_SE8_53") (pintype "bidirectional"))
      (node (ref "IC201") (pin "14") (pinfunction "~{INT_SDO_C}_14") (pintype "output"))
      (node (ref "LED201") (pin "C") (pinfunction "C_C") (pintype "passive"))
    )
    (net (code "152") (name "~{SCS_429}") (class "Default")
      (node (ref "IC101") (pin "58") (pinfunction "PTB10/SPI1_PCS0_58") (pintype "bidirectional"))
      (node (ref "IC201") (pin "7") (pinfunction "~{SCS_C}_7") (pintype "input"))
    )
  )
)
